# brushless_module_v2.net
KiCad netlist of a schematic drawn in EAGLE
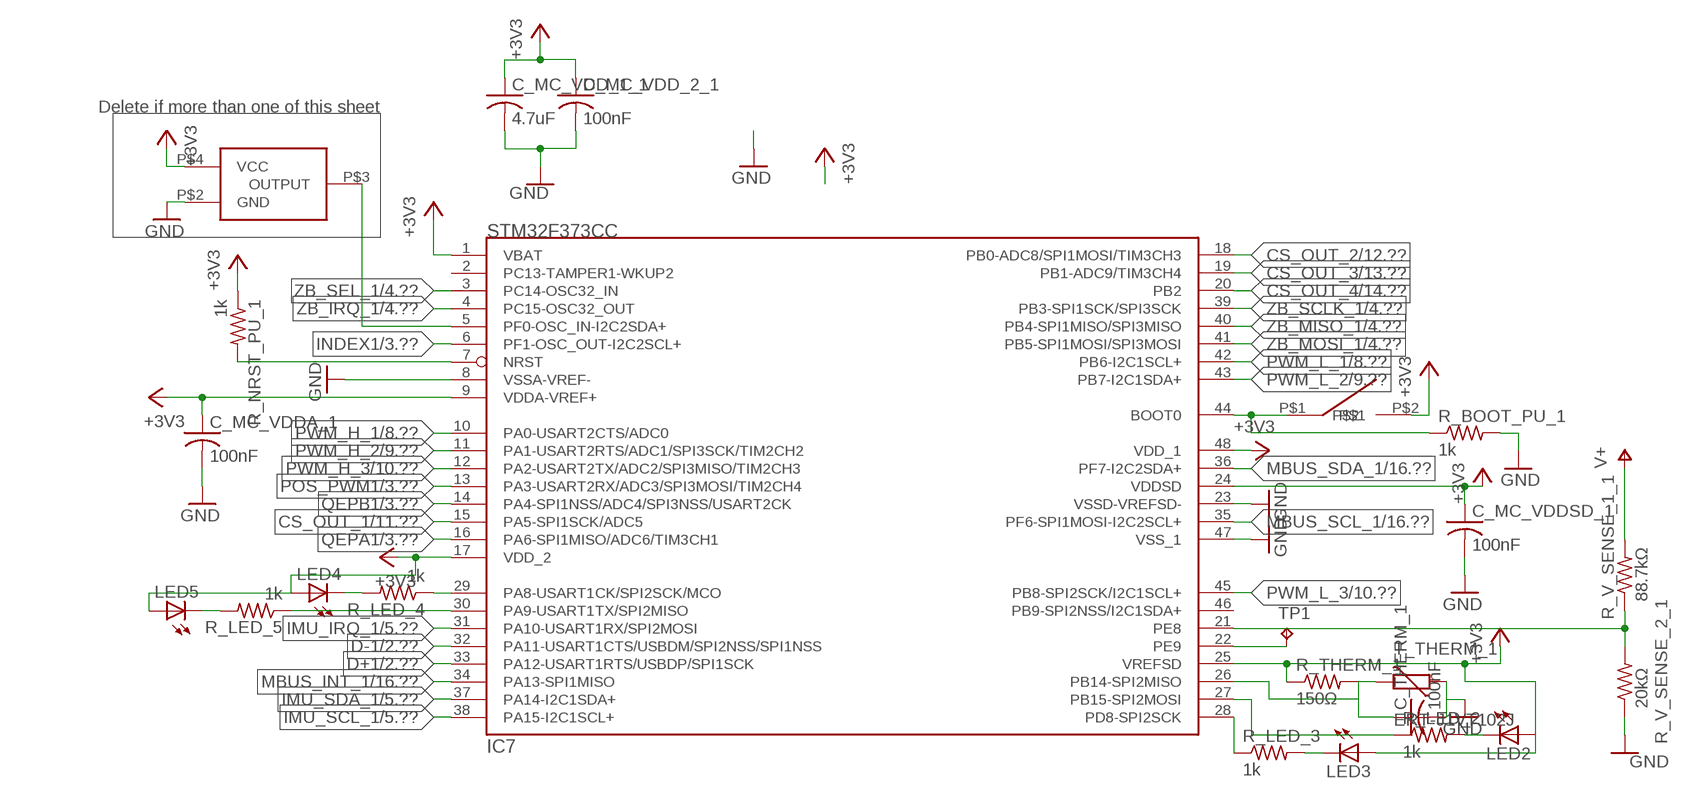
[diagram p0: schematic, sheet 1]
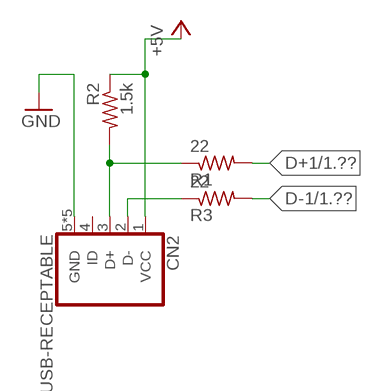
[diagram p1: schematic, sheet 2]
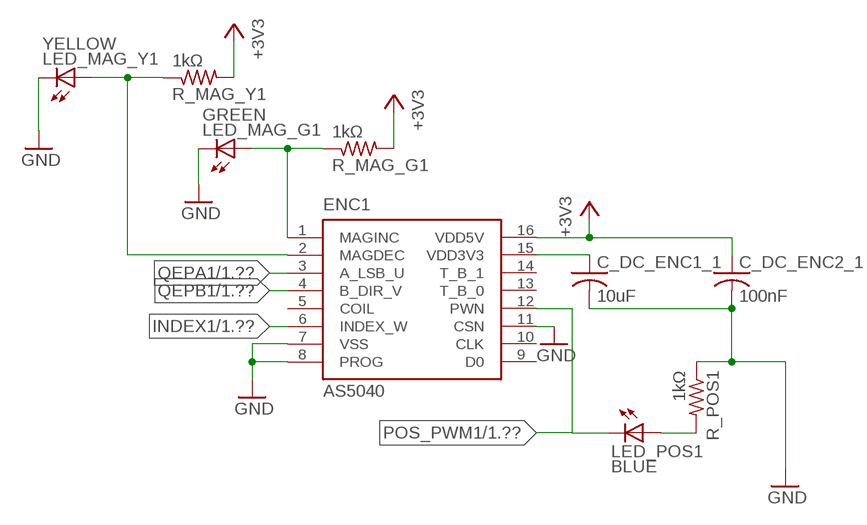
[diagram p2: schematic, sheet 3]
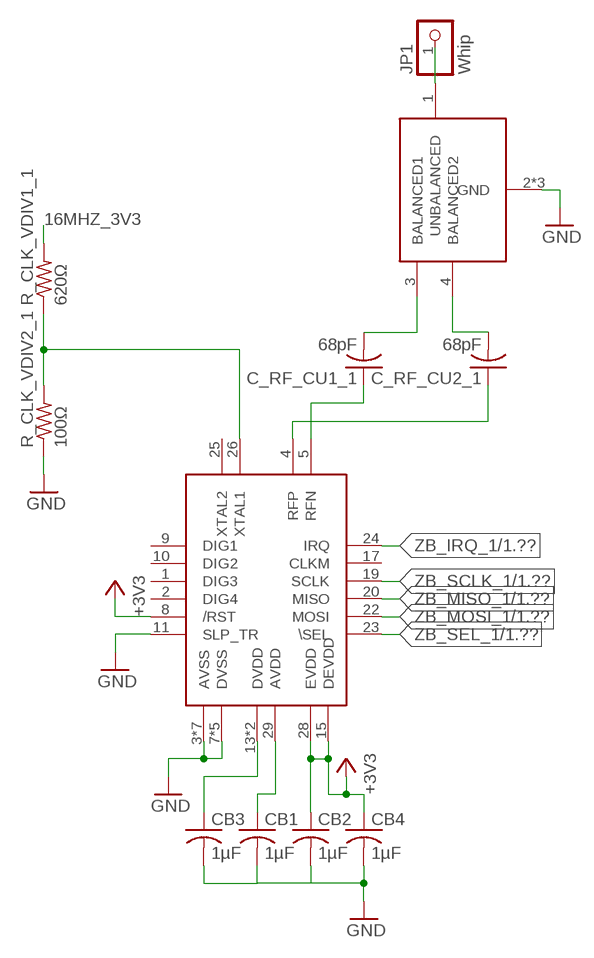
[diagram p3: schematic, sheet 4]
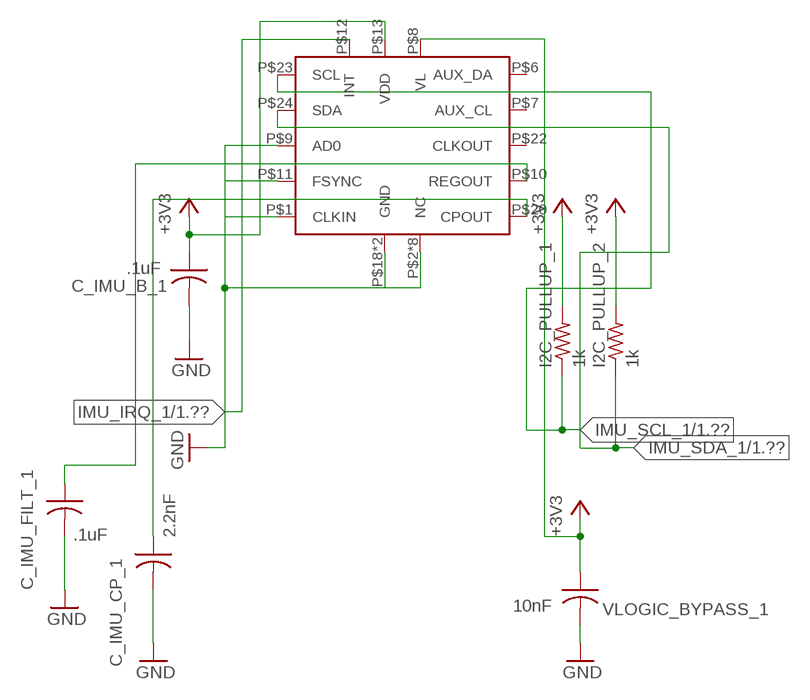
[diagram p4: schematic, sheet 5]
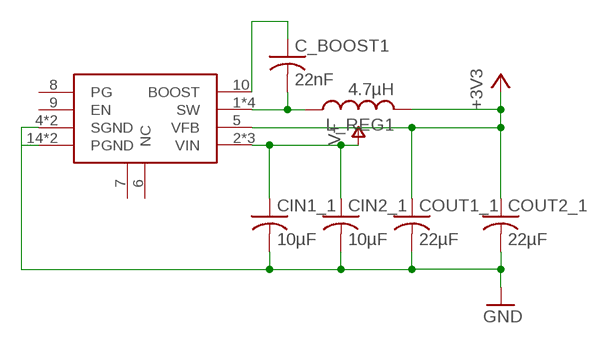
[diagram p5: schematic, sheet 6]
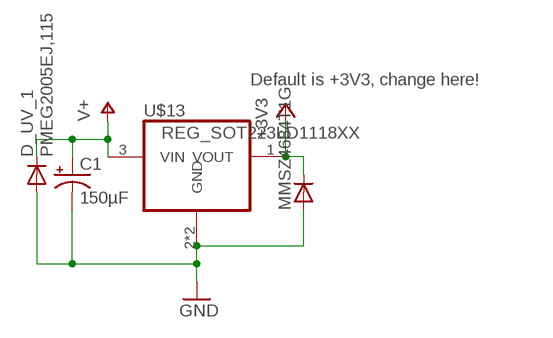
[diagram p6: schematic, sheet 7]
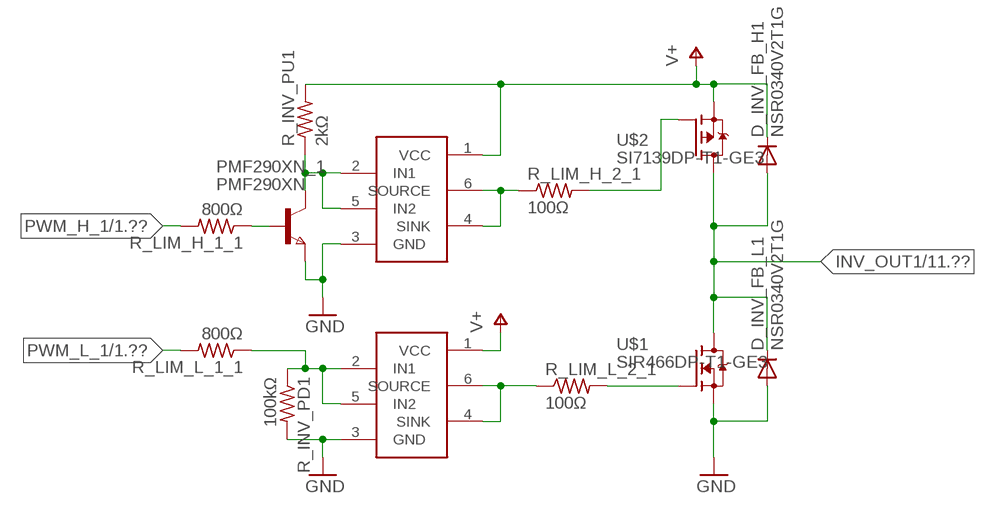
[diagram p7: schematic, sheet 8]
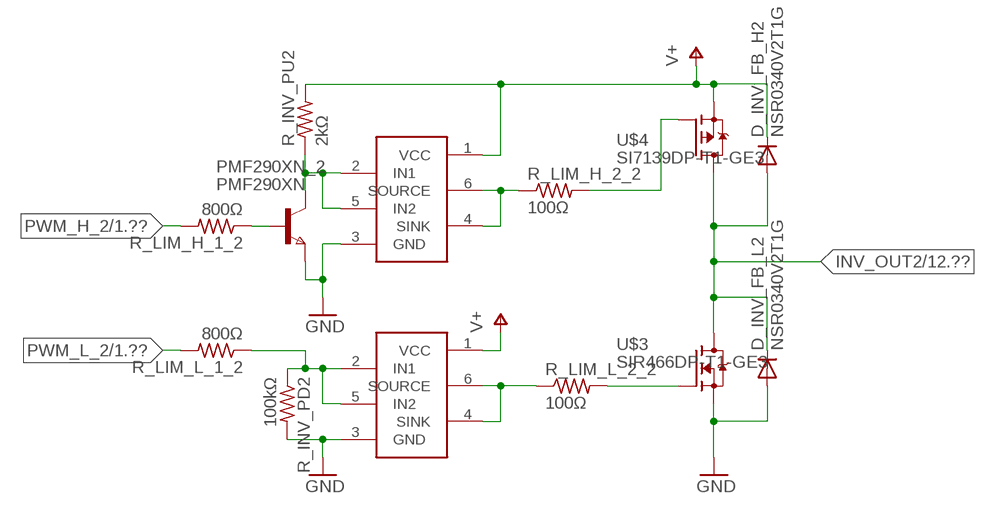
[diagram p8: schematic, sheet 9]
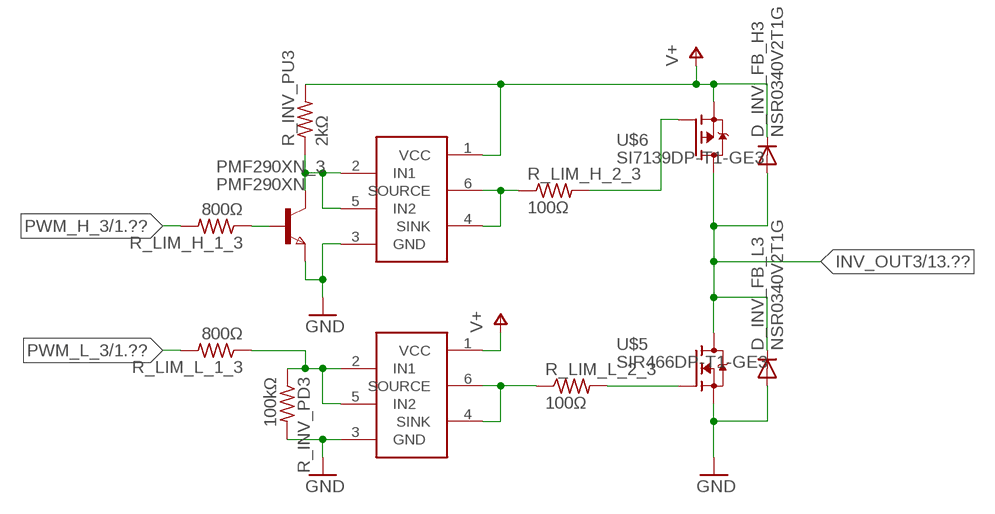
[diagram p9: schematic, sheet 10]
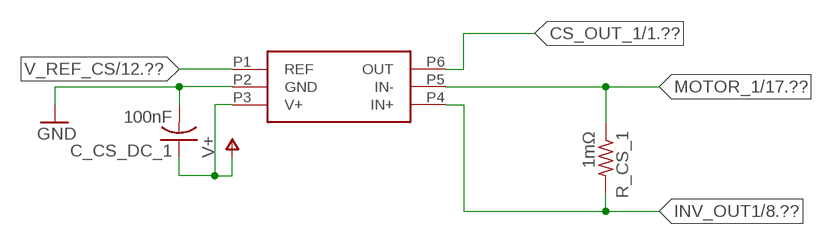
[diagram p10: schematic, sheet 11]
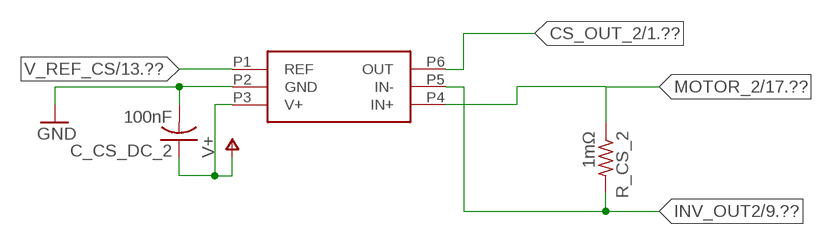
[diagram p11: schematic, sheet 12]
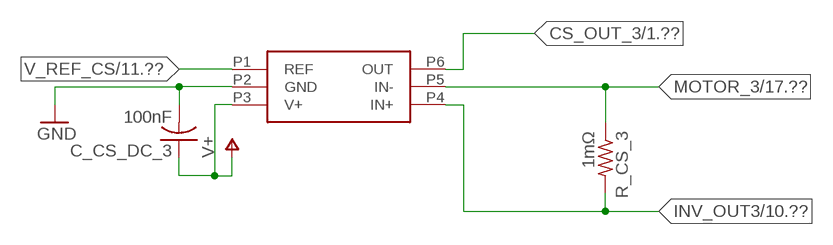
[diagram p12: schematic, sheet 13]
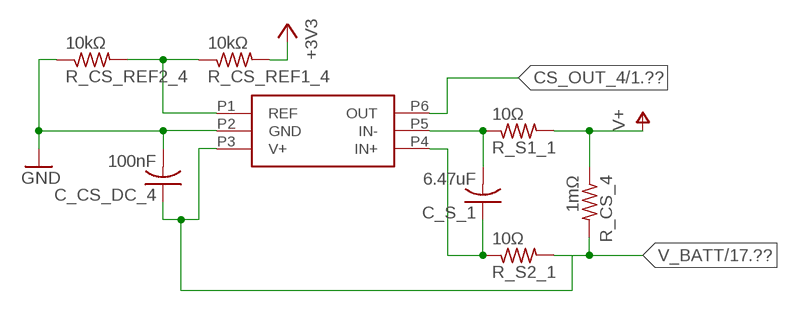
[diagram p13: schematic, sheet 14]
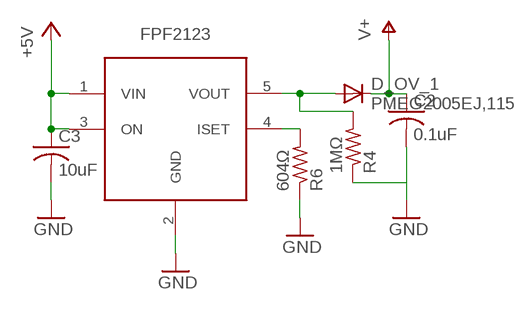
[diagram p14: schematic, sheet 15]
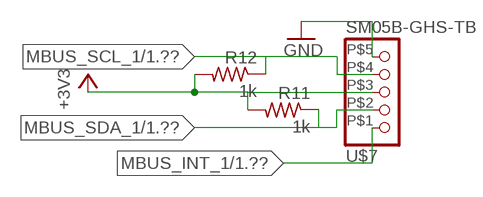
[diagram p15: schematic, sheet 16]
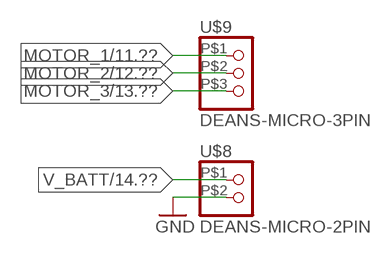
[diagram p16: schematic, sheet 17]

(export (version "E")
  (design (tool "Eeschema 10.0.6"))
  (components
    (comp (ref "C_DC_ENC1_1")
      (value "10uF")
      (footprint "eagle-import:C0603")
      (libsource (lib "eagle-import") (part "C-USC0603"))
    )
    (comp (ref "C_DC_ENC2_1")
      (value "100nF")
      (footprint "eagle-import:C0603")
      (libsource (lib "eagle-import") (part "C-USC0603"))
    )
    (comp (ref "ENC1")
      (value "AS5040")
      (footprint "eagle-import:SSOP16")
      (fields (field (name "MPN") "AS5040ASSU"))
      (libsource (lib "eagle-import") (part "AS5040"))
    )
    (comp (ref "LED_MAG_G1")
      (value "GREEN")
      (footprint "eagle-import:CHIP-LED0603")
      (libsource (lib "eagle-import") (part "LEDCHIP-LED0603"))
    )
    (comp (ref "LED_MAG_Y1")
      (value "YELLOW")
      (footprint "eagle-import:CHIP-LED0603")
      (libsource (lib "eagle-import") (part "LEDCHIP-LED0603"))
    )
    (comp (ref "LED_POS1")
      (value "BLUE")
      (footprint "eagle-import:CHIP-LED0603")
      (libsource (lib "eagle-import") (part "LEDCHIP-LED0603"))
    )
    (comp (ref "R_MAG_G1")
      (value "1kΩ")
      (footprint "eagle-import:R0603")
      (libsource (lib "eagle-import") (part "R-US_R0603"))
    )
    (comp (ref "R_MAG_Y1")
      (value "1kΩ")
      (footprint "eagle-import:R0603")
      (libsource (lib "eagle-import") (part "R-US_R0603"))
    )
    (comp (ref "R_POS1")
      (value "1kΩ")
      (footprint "eagle-import:R0603")
      (libsource (lib "eagle-import") (part "R-US_R0603"))
    )
    (comp (ref "U$8")
      (value "DEANS-MICRO-2PIN")
      (footprint "eagle-import:DEANS-MICRO-2PIN")
      (libsource (lib "eagle-import") (part "DEANS-MICRO-2PIN"))
    )
    (comp (ref "U$9")
      (value "DEANS-MICRO-3PIN")
      (footprint "eagle-import:DEANS-MICRO-3PIN")
      (libsource (lib "eagle-import") (part "DEANS-MICRO-3PIN"))
    )
    (comp (ref "C2")
      (value "0.1uF")
      (footprint "eagle-import:C0603")
      (libsource (lib "eagle-import") (part "C-USC0603"))
    )
    (comp (ref "C3")
      (value "10uF")
      (footprint "eagle-import:C0603")
      (libsource (lib "eagle-import") (part "C-USC0603"))
    )
    (comp (ref "D_OV_1")
      (value "PMEG2005EJ,115")
      (footprint "eagle-import:SOD323-W")
      (libsource (lib "eagle-import") (part "DIODE-SOD323-W"))
    )
    (comp (ref "FPF2123")
      (value "FPF2123")
      (footprint "eagle-import:SOT23-5L")
      (libsource (lib "eagle-import") (part "FPF2123"))
    )
    (comp (ref "R4")
      (value "1MΩ")
      (footprint "eagle-import:R0603")
      (libsource (lib "eagle-import") (part "R-US_R0603"))
    )
    (comp (ref "R6")
      (value "604Ω")
      (footprint "eagle-import:R0603")
      (libsource (lib "eagle-import") (part "R-US_R0603"))
    )
    (comp (ref "C_MC_VDDA_1")
      (value "100nF")
      (footprint "eagle-import:C0603")
      (libsource (lib "eagle-import") (part "C-USC0603"))
    )
    (comp (ref "C_MC_VDDSD_1")
      (value "100nF")
      (footprint "eagle-import:C0603")
      (libsource (lib "eagle-import") (part "C-USC0603"))
    )
    (comp (ref "C_MC_VDD_1_1")
      (value "4.7uF")
      (footprint "eagle-import:C0603")
      (libsource (lib "eagle-import") (part "C-USC0603"))
    )
    (comp (ref "C_MC_VDD_2_1")
      (value "100nF")
      (footprint "eagle-import:C0603")
      (libsource (lib "eagle-import") (part "C-USC0603"))
    )
    (comp (ref "C_THERM_1")
      (value "100nF")
      (footprint "eagle-import:C0603")
      (libsource (lib "eagle-import") (part "C-USC0603"))
    )
    (comp (ref "IC7")
      (value "STM32F373CC")
      (footprint "eagle-import:LQFP48")
      (libsource (lib "eagle-import") (part "STM32F373CC"))
    )
    (comp (ref "LED2")
      (value "LEDCHIPLED_0603")
      (footprint "eagle-import:CHIPLED_0603")
      (libsource (lib "eagle-import") (part "LEDCHIPLED_0603"))
    )
    (comp (ref "LED3")
      (value "LEDCHIPLED_0603")
      (footprint "eagle-import:CHIPLED_0603")
      (libsource (lib "eagle-import") (part "LEDCHIPLED_0603"))
    )
    (comp (ref "LED4")
      (value "LEDCHIPLED_0603")
      (footprint "eagle-import:CHIPLED_0603")
      (libsource (lib "eagle-import") (part "LEDCHIPLED_0603"))
    )
    (comp (ref "LED5")
      (value "LEDCHIPLED_0603")
      (footprint "eagle-import:CHIPLED_0603")
      (libsource (lib "eagle-import") (part "LEDCHIPLED_0603"))
    )
    (comp (ref "OSC1")
      (value "FOX924B")
      (footprint "eagle-import:4-SMD_5X3.2")
      (libsource (lib "eagle-import") (part "FOX924B"))
    )
    (comp (ref "R_BOOT_PU_1")
      (value "1k")
      (footprint "eagle-import:R0603")
      (libsource (lib "eagle-import") (part "R-US_R0603"))
    )
    (comp (ref "R_LED_2")
      (value "1k")
      (footprint "eagle-import:R0603")
      (libsource (lib "eagle-import") (part "R-US_R0603"))
    )
    (comp (ref "R_LED_3")
      (value "1k")
      (footprint "eagle-import:R0603")
      (libsource (lib "eagle-import") (part "R-US_R0603"))
    )
    (comp (ref "R_LED_4")
      (value "1k")
      (footprint "eagle-import:R0603")
      (libsource (lib "eagle-import") (part "R-US_R0603"))
    )
    (comp (ref "R_LED_5")
      (value "1k")
      (footprint "eagle-import:R0603")
      (libsource (lib "eagle-import") (part "R-US_R0603"))
    )
    (comp (ref "R_NRST_PU_1")
      (value "1k")
      (footprint "eagle-import:R0603")
      (libsource (lib "eagle-import") (part "R-US_R0603"))
    )
    (comp (ref "R_THERM_1")
      (value "150Ω")
      (footprint "eagle-import:R0603")
      (libsource (lib "eagle-import") (part "R-US_R0603"))
    )
    (comp (ref "R_V_SENSE_1_1")
      (value "88.7kΩ")
      (footprint "eagle-import:R0603")
      (libsource (lib "eagle-import") (part "R-US_R0603"))
    )
    (comp (ref "R_V_SENSE_2_1")
      (value "20kΩ")
      (footprint "eagle-import:R0603")
      (libsource (lib "eagle-import") (part "R-US_R0603"))
    )
    (comp (ref "SW1")
      (value "B3U")
      (footprint "eagle-import:B3U")
      (libsource (lib "eagle-import") (part "B3U"))
    )
    (comp (ref "TP1")
      (value "TPTP10R")
      (footprint "eagle-import:TP10R")
      (libsource (lib "eagle-import") (part "TPTP10R"))
    )
    (comp (ref "T_THERM_1")
      (value "ERT-J1VT102J")
      (footprint "eagle-import:CT_CN0603")
      (libsource (lib "eagle-import") (part "VARISTORCN0603"))
    )
    (comp (ref "D_INV_FB_H1")
      (value "NSR0340V2T1G")
      (footprint "eagle-import:SOD523")
      (libsource (lib "eagle-import") (part "DIODE-SOD523"))
    )
    (comp (ref "D_INV_FB_L1")
      (value "NSR0340V2T1G")
      (footprint "eagle-import:SOD523")
      (libsource (lib "eagle-import") (part "DIODE-SOD523"))
    )
    (comp (ref "PMF290XN_1")
      (value "PMF290XN")
      (footprint "eagle-import:SOT323")
      (fields (field (name "MPN") "DSS4160U-7"))
      (libsource (lib "eagle-import") (part "NPNSOT323"))
    )
    (comp (ref "R_INV_PD1")
      (value "100kΩ")
      (footprint "eagle-import:R0603")
      (fields (field (name "PART#") "RNCP0603FTD825RCT-ND"))
      (libsource (lib "eagle-import") (part "R-US_R0603"))
    )
    (comp (ref "R_INV_PU1")
      (value "2kΩ")
      (footprint "eagle-import:R0603")
      (libsource (lib "eagle-import") (part "R-US_R0603"))
    )
    (comp (ref "R_LIM_H_1_1")
      (value "800Ω")
      (footprint "eagle-import:R0603")
      (libsource (lib "eagle-import") (part "R-US_R0603"))
    )
    (comp (ref "R_LIM_H_2_1")
      (value "100Ω")
      (footprint "eagle-import:R0603")
      (libsource (lib "eagle-import") (part "R-US_R0603"))
    )
    (comp (ref "R_LIM_L_1_1")
      (value "800Ω")
      (footprint "eagle-import:R0603")
      (libsource (lib "eagle-import") (part "R-US_R0603"))
    )
    (comp (ref "R_LIM_L_2_1")
      (value "100Ω")
      (footprint "eagle-import:R0603")
      (libsource (lib "eagle-import") (part "R-US_R0603"))
    )
    (comp (ref "U$1")
      (value "SIR466DP-T1-GE3")
      (footprint "eagle-import:S0-8-POWERPAK")
      (libsource (lib "eagle-import") (part "SIR466DP-T1-GE3"))
    )
    (comp (ref "U$2")
      (value "SI7139DP-T1-GE3")
      (footprint "eagle-import:S0-8-POWERPAK")
      (libsource (lib "eagle-import") (part "SI7139DP-T1-GE3"))
    )
    (comp (ref "ZXGD3004E6_H_1")
      (value "ZXGD3004E6")
      (footprint "eagle-import:SOT23-6")
      (libsource (lib "eagle-import") (part "ZXGD3004E6"))
    )
    (comp (ref "ZXGD3004E6_L_1")
      (value "ZXGD3004E6")
      (footprint "eagle-import:SOT23-6")
      (libsource (lib "eagle-import") (part "ZXGD3004E6"))
    )
    (comp (ref "CN2")
      (value "USB-RECEPTABLE")
      (footprint "eagle-import:FCI-10103594-0001LF")
      (libsource (lib "eagle-import") (part "USB-RECEPTABLE"))
    )
    (comp (ref "R1")
      (value "22")
      (footprint "eagle-import:R0603")
      (libsource (lib "eagle-import") (part "R-US_R0603"))
    )
    (comp (ref "R2")
      (value "1.5k")
      (footprint "eagle-import:R0603")
      (libsource (lib "eagle-import") (part "R-US_R0603"))
    )
    (comp (ref "R3")
      (value "22")
      (footprint "eagle-import:R0603")
      (libsource (lib "eagle-import") (part "R-US_R0603"))
    )
    (comp (ref "C1")
      (value "150µF")
      (footprint "eagle-import:D_7343-31R")
      (libsource (lib "eagle-import") (part "CPOL-USD/7343-31R"))
    )
    (comp (ref "D_UV_1")
      (value "PMEG2005EJ,115")
      (footprint "eagle-import:SOD323-W")
      (libsource (lib "eagle-import") (part "DIODE-SOD323-W"))
    )
    (comp (ref "MMSZ4684T1G")
      (value "D-SOD123")
      (footprint "eagle-import:SOD123")
      (libsource (lib "eagle-import") (part "D-SOD123"))
    )
    (comp (ref "U$13")
      (value "REG_SOT223LD1118XX")
      (footprint "eagle-import:SOT-223")
      (libsource (lib "eagle-import") (part "REG_SOT223LD1118XX"))
    )
    (comp (ref "R11")
      (value "1k")
      (footprint "eagle-import:R0603")
      (libsource (lib "eagle-import") (part "R-US_R0603"))
    )
    (comp (ref "R12")
      (value "1k")
      (footprint "eagle-import:R0603")
      (libsource (lib "eagle-import") (part "R-US_R0603"))
    )
    (comp (ref "U$7")
      (value "SM05B-GHS-TB")
      (footprint "eagle-import:SM05B-GHS-TB")
      (libsource (lib "eagle-import") (part "SM05B-GHS-TB"))
    )
    (comp (ref "D_INV_FB_H2")
      (value "NSR0340V2T1G")
      (footprint "eagle-import:SOD523")
      (libsource (lib "eagle-import") (part "DIODE-SOD523"))
    )
    (comp (ref "D_INV_FB_L2")
      (value "NSR0340V2T1G")
      (footprint "eagle-import:SOD523")
      (libsource (lib "eagle-import") (part "DIODE-SOD523"))
    )
    (comp (ref "PMF290XN_2")
      (value "PMF290XN")
      (footprint "eagle-import:SOT323")
      (fields (field (name "MPN") "DSS4160U-7"))
      (libsource (lib "eagle-import") (part "NPNSOT323"))
    )
    (comp (ref "R_INV_PD2")
      (value "100kΩ")
      (footprint "eagle-import:R0603")
      (fields (field (name "PART#") "RNCP0603FTD825RCT-ND"))
      (libsource (lib "eagle-import") (part "R-US_R0603"))
    )
    (comp (ref "R_INV_PU2")
      (value "2kΩ")
      (footprint "eagle-import:R0603")
      (libsource (lib "eagle-import") (part "R-US_R0603"))
    )
    (comp (ref "R_LIM_H_1_2")
      (value "800Ω")
      (footprint "eagle-import:R0603")
      (libsource (lib "eagle-import") (part "R-US_R0603"))
    )
    (comp (ref "R_LIM_H_2_2")
      (value "100Ω")
      (footprint "eagle-import:R0603")
      (libsource (lib "eagle-import") (part "R-US_R0603"))
    )
    (comp (ref "R_LIM_L_1_2")
      (value "800Ω")
      (footprint "eagle-import:R0603")
      (libsource (lib "eagle-import") (part "R-US_R0603"))
    )
    (comp (ref "R_LIM_L_2_2")
      (value "100Ω")
      (footprint "eagle-import:R0603")
      (libsource (lib "eagle-import") (part "R-US_R0603"))
    )
    (comp (ref "U$3")
      (value "SIR466DP-T1-GE3")
      (footprint "eagle-import:S0-8-POWERPAK")
      (libsource (lib "eagle-import") (part "SIR466DP-T1-GE3"))
    )
    (comp (ref "U$4")
      (value "SI7139DP-T1-GE3")
      (footprint "eagle-import:S0-8-POWERPAK")
      (libsource (lib "eagle-import") (part "SI7139DP-T1-GE3"))
    )
    (comp (ref "ZXGD3004E6_H_2")
      (value "ZXGD3004E6")
      (footprint "eagle-import:SOT23-6")
      (libsource (lib "eagle-import") (part "ZXGD3004E6"))
    )
    (comp (ref "ZXGD3004E6_L_2")
      (value "ZXGD3004E6")
      (footprint "eagle-import:SOT23-6")
      (libsource (lib "eagle-import") (part "ZXGD3004E6"))
    )
    (comp (ref "C_IMU_B_1")
      (value ".1uF")
      (footprint "eagle-import:C0603")
      (libsource (lib "eagle-import") (part "C-USC0603"))
    )
    (comp (ref "C_IMU_CP_1")
      (value "2.2nF")
      (footprint "eagle-import:C0603")
      (libsource (lib "eagle-import") (part "C-USC0603"))
    )
    (comp (ref "C_IMU_FILT_1")
      (value ".1uF")
      (footprint "eagle-import:C0603")
      (libsource (lib "eagle-import") (part "C-USC0603"))
    )
    (comp (ref "I2C_PULLUP_1")
      (value "1k")
      (footprint "eagle-import:R0603")
      (libsource (lib "eagle-import") (part "R-US_R0603"))
    )
    (comp (ref "I2C_PULLUP_2")
      (value "1k")
      (footprint "eagle-import:R0603")
      (libsource (lib "eagle-import") (part "R-US_R0603"))
    )
    (comp (ref "U$10")
      (value "MPU-6050")
      (footprint "eagle-import:QFN24")
      (libsource (lib "eagle-import") (part "MPU-6050"))
    )
    (comp (ref "VLOGIC_BYPASS_1")
      (value "10nF")
      (footprint "eagle-import:C0603")
      (libsource (lib "eagle-import") (part "C-USC0603"))
    )
    (comp (ref "CIN1_1")
      (value "10µF")
      (footprint "eagle-import:C0805")
      (libsource (lib "eagle-import") (part "C-USC0805"))
    )
    (comp (ref "CIN2_1")
      (value "10µF")
      (footprint "eagle-import:C0805")
      (libsource (lib "eagle-import") (part "C-USC0805"))
    )
    (comp (ref "COUT1_1")
      (value "22µF")
      (footprint "eagle-import:C0603")
      (libsource (lib "eagle-import") (part "C-USC0603"))
    )
    (comp (ref "COUT2_1")
      (value "22µF")
      (footprint "eagle-import:C0603")
      (libsource (lib "eagle-import") (part "C-USC0603"))
    )
    (comp (ref "C_BOOST1")
      (value "22nF")
      (footprint "eagle-import:C0603")
      (libsource (lib "eagle-import") (part "C-USC0603"))
    )
    (comp (ref "L_REG1")
      (value "4.7µH")
      (footprint "eagle-import:VLC5045")
      (libsource (lib "eagle-import") (part "VLC5045"))
    )
    (comp (ref "SW_REG1")
      (value "MCP16323")
      (footprint "eagle-import:QFN16")
      (libsource (lib "eagle-import") (part "MCP16323"))
    )
    (comp (ref "CS_1")
      (value "INA21X")
      (footprint "eagle-import:SC70")
      (libsource (lib "eagle-import") (part "INA21X"))
    )
    (comp (ref "C_CS_DC_1")
      (value "100nF")
      (footprint "eagle-import:C0603")
      (libsource (lib "eagle-import") (part "C-USC0603"))
    )
    (comp (ref "R_CS_1")
      (value "1mΩ")
      (footprint "eagle-import:R1206")
      (libsource (lib "eagle-import") (part "R-US_R1206"))
    )
    (comp (ref "BALUN1")
      (value "0896FB15A0100")
      (footprint "eagle-import:0896FB15A0100")
      (libsource (lib "eagle-import") (part "0896FB15A0100"))
    )
    (comp (ref "CB1")
      (value "1µF")
      (footprint "eagle-import:C0603")
      (libsource (lib "eagle-import") (part "C-USC0603"))
    )
    (comp (ref "CB2")
      (value "1µF")
      (footprint "eagle-import:C0603")
      (libsource (lib "eagle-import") (part "C-USC0603"))
    )
    (comp (ref "CB3")
      (value "1µF")
      (footprint "eagle-import:C0603")
      (libsource (lib "eagle-import") (part "C-USC0603"))
    )
    (comp (ref "CB4")
      (value "1µF")
      (footprint "eagle-import:C0603")
      (libsource (lib "eagle-import") (part "C-USC0603"))
    )
    (comp (ref "C_RF_CU1_1")
      (value "68pF")
      (footprint "eagle-import:C0603")
      (libsource (lib "eagle-import") (part "C-USC0603"))
    )
    (comp (ref "C_RF_CU2_1")
      (value "68pF")
      (footprint "eagle-import:C0603")
      (libsource (lib "eagle-import") (part "C-USC0603"))
    )
    (comp (ref "JP1")
      (value "Whip")
      (footprint "eagle-import:1X01M")
      (libsource (lib "eagle-import") (part "PINHD-1X01_2.00"))
    )
    (comp (ref "RADIO1")
      (value "AT86RF")
      (footprint "eagle-import:QFNN32")
      (libsource (lib "eagle-import") (part "AT86RF"))
    )
    (comp (ref "R_CLK_VDIV1_1")
      (value "620Ω")
      (footprint "eagle-import:R0603")
      (libsource (lib "eagle-import") (part "R-US_R0603"))
    )
    (comp (ref "R_CLK_VDIV2_1")
      (value "100Ω")
      (footprint "eagle-import:R0603")
      (libsource (lib "eagle-import") (part "R-US_R0603"))
    )
    (comp (ref "D_INV_FB_H3")
      (value "NSR0340V2T1G")
      (footprint "eagle-import:SOD523")
      (libsource (lib "eagle-import") (part "DIODE-SOD523"))
    )
    (comp (ref "D_INV_FB_L3")
      (value "NSR0340V2T1G")
      (footprint "eagle-import:SOD523")
      (libsource (lib "eagle-import") (part "DIODE-SOD523"))
    )
    (comp (ref "PMF290XN_3")
      (value "PMF290XN")
      (footprint "eagle-import:SOT323")
      (fields (field (name "MPN") "DSS4160U-7"))
      (libsource (lib "eagle-import") (part "NPNSOT323"))
    )
    (comp (ref "R_INV_PD3")
      (value "100kΩ")
      (footprint "eagle-import:R0603")
      (fields (field (name "PART#") "RNCP0603FTD825RCT-ND"))
      (libsource (lib "eagle-import") (part "R-US_R0603"))
    )
    (comp (ref "R_INV_PU3")
      (value "2kΩ")
      (footprint "eagle-import:R0603")
      (libsource (lib "eagle-import") (part "R-US_R0603"))
    )
    (comp (ref "R_LIM_H_1_3")
      (value "800Ω")
      (footprint "eagle-import:R0603")
      (libsource (lib "eagle-import") (part "R-US_R0603"))
    )
    (comp (ref "R_LIM_H_2_3")
      (value "100Ω")
      (footprint "eagle-import:R0603")
      (libsource (lib "eagle-import") (part "R-US_R0603"))
    )
    (comp (ref "R_LIM_L_1_3")
      (value "800Ω")
      (footprint "eagle-import:R0603")
      (libsource (lib "eagle-import") (part "R-US_R0603"))
    )
    (comp (ref "R_LIM_L_2_3")
      (value "100Ω")
      (footprint "eagle-import:R0603")
      (libsource (lib "eagle-import") (part "R-US_R0603"))
    )
    (comp (ref "U$5")
      (value "SIR466DP-T1-GE3")
      (footprint "eagle-import:S0-8-POWERPAK")
      (libsource (lib "eagle-import") (part "SIR466DP-T1-GE3"))
    )
    (comp (ref "U$6")
      (value "SI7139DP-T1-GE3")
      (footprint "eagle-import:S0-8-POWERPAK")
      (libsource (lib "eagle-import") (part "SI7139DP-T1-GE3"))
    )
    (comp (ref "ZXGD3004E6_H_3")
      (value "ZXGD3004E6")
      (footprint "eagle-import:SOT23-6")
      (libsource (lib "eagle-import") (part "ZXGD3004E6"))
    )
    (comp (ref "ZXGD3004E6_L_3")
      (value "ZXGD3004E6")
      (footprint "eagle-import:SOT23-6")
      (libsource (lib "eagle-import") (part "ZXGD3004E6"))
    )
    (comp (ref "CS_4")
      (value "INA21X")
      (footprint "eagle-import:SC70")
      (libsource (lib "eagle-import") (part "INA21X"))
    )
    (comp (ref "C_CS_DC_4")
      (value "100nF")
      (footprint "eagle-import:C0603")
      (libsource (lib "eagle-import") (part "C-USC0603"))
    )
    (comp (ref "C_S_1")
      (value "6.47uF")
      (footprint "eagle-import:C0603")
      (libsource (lib "eagle-import") (part "C-USC0603"))
    )
    (comp (ref "R_CS_4")
      (value "1mΩ")
      (footprint "eagle-import:R1206")
      (libsource (lib "eagle-import") (part "R-US_R1206"))
    )
    (comp (ref "R_CS_REF1_4")
      (value "10kΩ")
      (footprint "eagle-import:R0603")
      (libsource (lib "eagle-import") (part "R-US_R0603"))
    )
    (comp (ref "R_CS_REF2_4")
      (value "10kΩ")
      (footprint "eagle-import:R0603")
      (libsource (lib "eagle-import") (part "R-US_R0603"))
    )
    (comp (ref "R_S1_1")
      (value "10Ω")
      (footprint "eagle-import:R0603")
      (libsource (lib "eagle-import") (part "R-US_R0603"))
    )
    (comp (ref "R_S2_1")
      (value "10Ω")
      (footprint "eagle-import:R0603")
      (libsource (lib "eagle-import") (part "R-US_R0603"))
    )
    (comp (ref "CS_2")
      (value "INA21X")
      (footprint "eagle-import:SC70")
      (libsource (lib "eagle-import") (part "INA21X"))
    )
    (comp (ref "C_CS_DC_2")
      (value "100nF")
      (footprint "eagle-import:C0603")
      (libsource (lib "eagle-import") (part "C-USC0603"))
    )
    (comp (ref "R_CS_2")
      (value "1mΩ")
      (footprint "eagle-import:R1206")
      (libsource (lib "eagle-import") (part "R-US_R1206"))
    )
    (comp (ref "CS_3")
      (value "INA21X")
      (footprint "eagle-import:SC70")
      (libsource (lib "eagle-import") (part "INA21X"))
    )
    (comp (ref "C_CS_DC_3")
      (value "100nF")
      (footprint "eagle-import:C0603")
      (libsource (lib "eagle-import") (part "C-USC0603"))
    )
    (comp (ref "R_CS_3")
      (value "1mΩ")
      (footprint "eagle-import:R1206")
      (libsource (lib "eagle-import") (part "R-US_R1206"))
    )
  )
  (nets
    (net (code "1") (name "+3V3") (class "Default")
      (node (ref "CB2") (pin "1") (pinfunction "1_1") (pintype "passive"))
      (node (ref "CB4") (pin "1") (pinfunction "1_1") (pintype "passive"))
      (node (ref "COUT1_1") (pin "1") (pinfunction "1_1") (pintype "passive"))
      (node (ref "COUT2_1") (pin "1") (pinfunction "1_1") (pintype "passive"))
      (node (ref "C_DC_ENC2_1") (pin "1") (pinfunction "1_1") (pintype "passive"))
      (node (ref "C_IMU_B_1") (pin "1") (pinfunction "1_1") (pintype "passive"))
      (node (ref "C_MC_VDDA_1") (pin "1") (pinfunction "1_1") (pintype "passive"))
      (node (ref "C_MC_VDDSD_1") (pin "1") (pinfunction "1_1") (pintype "passive"))
      (node (ref "C_MC_VDD_1_1") (pin "1") (pinfunction "1_1") (pintype "passive"))
      (node (ref "C_MC_VDD_2_1") (pin "1") (pinfunction "1_1") (pintype "passive"))
      (node (ref "ENC1") (pin "16") (pinfunction "VDD5V_16") (pintype "passive"))
      (node (ref "I2C_PULLUP_1") (pin "2") (pinfunction "2_2") (pintype "passive"))
      (node (ref "I2C_PULLUP_2") (pin "2") (pinfunction "2_2") (pintype "passive"))
      (node (ref "IC7") (pin "1") (pinfunction "VBAT_1") (pintype "power_in"))
      (node (ref "IC7") (pin "17") (pinfunction "VDD_2_17") (pintype "bidirectional"))
      (node (ref "IC7") (pin "24") (pinfunction "VDDSD_24") (pintype "power_in"))
      (node (ref "IC7") (pin "25") (pinfunction "VREFSD_25") (pintype "bidirectional"))
      (node (ref "IC7") (pin "48") (pinfunction "VDD_1_48") (pintype "power_in"))
      (node (ref "IC7") (pin "9") (pinfunction "VDDA-VREF+_9") (pintype "power_in"))
      (node (ref "LED2") (pin "A") (pinfunction "A_A") (pintype "passive"))
      (node (ref "LED3") (pin "A") (pinfunction "A_A") (pintype "passive"))
      (node (ref "LED4") (pin "A") (pinfunction "A_A") (pintype "passive"))
      (node (ref "LED5") (pin "A") (pinfunction "A_A") (pintype "passive"))
      (node (ref "L_REG1") (pin "2") (pinfunction "2_2") (pintype "passive"))
      (node (ref "MMSZ4684T1G") (pin "1") (pinfunction "C_1") (pintype "passive"))
      (node (ref "OSC1") (pin "P$4") (pinfunction "VCC_P$4") (pintype "bidirectional"))
      (node (ref "R11") (pin "2") (pinfunction "2_2") (pintype "passive"))
      (node (ref "R12") (pin "2") (pinfunction "2_2") (pintype "passive"))
      (node (ref "RADIO1") (pin "15") (pinfunction "DEVDD_15") (pintype "power_in"))
      (node (ref "RADIO1") (pin "28") (pinfunction "EVDD_28") (pintype "power_in"))
      (node (ref "RADIO1") (pin "8") (pinfunction "/RST_8") (pintype "input"))
      (node (ref "R_CS_REF1_4") (pin "2") (pinfunction "2_2") (pintype "passive"))
      (node (ref "R_MAG_G1") (pin "2") (pinfunction "2_2") (pintype "passive"))
      (node (ref "R_MAG_Y1") (pin "2") (pinfunction "2_2") (pintype "passive"))
      (node (ref "R_NRST_PU_1") (pin "1") (pinfunction "1_1") (pintype "passive"))
      (node (ref "R_THERM_1") (pin "1") (pinfunction "1_1") (pintype "passive"))
      (node (ref "SW1") (pin "P$2") (pinfunction "P$2_P$2") (pintype "bidirectional"))
      (node (ref "SW_REG1") (pin "5") (pinfunction "VFB_5") (pintype "bidirectional"))
      (node (ref "U$10") (pin "P$13") (pinfunction "VDD_P$13") (pintype "bidirectional"))
      (node (ref "U$10") (pin "P$8") (pinfunction "VL_P$8") (pintype "bidirectional"))
      (node (ref "U$13") (pin "1") (pinfunction "VOUT_1") (pintype "output"))
      (node (ref "U$7") (pin "P$3") (pinfunction "3_P$3") (pintype "passive"))
      (node (ref "VLOGIC_BYPASS_1") (pin "1") (pinfunction "1_1") (pintype "passive"))
    )
    (net (code "2") (name "+5V") (class "Default")
      (node (ref "C3") (pin "1") (pinfunction "1_1") (pintype "passive"))
      (node (ref "CN2") (pin "1") (pinfunction "VCC_1") (pintype "bidirectional"))
      (node (ref "FPF2123") (pin "1") (pinfunction "VIN_1") (pintype "bidirectional"))
      (node (ref "FPF2123") (pin "3") (pinfunction "ON_3") (pintype "bidirectional"))
      (node (ref "R2") (pin "1") (pinfunction "1_1") (pintype "passive"))
    )
    (net (code "3") (name "16MHZ_3V3") (class "Default")
      (node (ref "IC7") (pin "5") (pinfunction "PF0-OSC_IN-I2C2SDA+_5") (pintype "bidirectional"))
      (node (ref "OSC1") (pin "P$3") (pinfunction "OUTPUT_P$3") (pintype "bidirectional"))
      (node (ref "R_CLK_VDIV1_1") (pin "2") (pinfunction "2_2") (pintype "passive"))
    )
    (net (code "4") (name "CS_OUT_1") (class "Default")
      (node (ref "CS_1") (pin "P6") (pinfunction "OUT_P6") (pintype "output"))
      (node (ref "IC7") (pin "15") (pinfunction "PA5-SPI1SCK/ADC5_15") (pintype "bidirectional"))
    )
    (net (code "5") (name "CS_OUT_2") (class "Default")
      (node (ref "CS_2") (pin "P6") (pinfunction "OUT_P6") (pintype "output"))
      (node (ref "IC7") (pin "18") (pinfunction "PB0-ADC8/SPI1MOSI/TIM3CH3_18") (pintype "bidirectional"))
    )
    (net (code "6") (name "CS_OUT_3") (class "Default")
      (node (ref "CS_3") (pin "P6") (pinfunction "OUT_P6") (pintype "output"))
      (node (ref "IC7") (pin "19") (pinfunction "PB1-ADC9/TIM3CH4_19") (pintype "bidirectional"))
    )
    (net (code "7") (name "CS_OUT_4") (class "Default")
      (node (ref "CS_4") (pin "P6") (pinfunction "OUT_P6") (pintype "output"))
      (node (ref "IC7") (pin "20") (pinfunction "PB2_20") (pintype "bidirectional"))
    )
    (net (code "8") (name "D+1") (class "Default")
      (node (ref "IC7") (pin "33") (pinfunction "PA12-USART1RTS/USBDP/SPI1SCK_33") (pintype "bidirectional"))
      (node (ref "R1") (pin "2") (pinfunction "2_2") (pintype "passive"))
    )
    (net (code "9") (name "D-1") (class "Default")
      (node (ref "IC7") (pin "32") (pinfunction "PA11-USART1CTS/USBDM/SPI2NSS/SPI1NSS_32") (pintype "bidirectional"))
      (node (ref "R3") (pin "2") (pinfunction "2_2") (pintype "passive"))
    )
    (net (code "10") (name "GND") (class "Default")
      (node (ref "BALUN1") (pin "2") (pinfunction "GND_2") (pintype "power_in"))
      (node (ref "BALUN1") (pin "5") (pinfunction "GND_5") (pintype "power_in"))
      (node (ref "BALUN1") (pin "6") (pinfunction "GND_6") (pintype "power_in"))
      (node (ref "C1") (pin "-") (pinfunction "-_-") (pintype "passive"))
      (node (ref "C2") (pin "2") (pinfunction "2_2") (pintype "passive"))
      (node (ref "C3") (pin "2") (pinfunction "2_2") (pintype "passive"))
      (node (ref "CB1") (pin "2") (pinfunction "2_2") (pintype "passive"))
      (node (ref "CB2") (pin "2") (pinfunction "2_2") (pintype "passive"))
      (node (ref "CB3") (pin "2") (pinfunction "2_2") (pintype "passive"))
      (node (ref "CB4") (pin "2") (pinfunction "2_2") (pintype "passive"))
      (node (ref "CIN1_1") (pin "2") (pinfunction "2_2") (pintype "passive"))
      (node (ref "CIN2_1") (pin "2") (pinfunction "2_2") (pintype "passive"))
      (node (ref "CN2") (pin "5") (pinfunction "GND_5") (pintype "bidirectional"))
      (node (ref "CN2") (pin "P$1") (pinfunction "GND_P$1") (pintype "bidirectional"))
      (node (ref "CN2") (pin "P$2") (pinfunction "GND_P$2") (pintype "bidirectional"))
      (node (ref "CN2") (pin "P$3") (pinfunction "GND_P$3") (pintype "bidirectional"))
      (node (ref "CN2") (pin "P$4") (pinfunction "GND_P$4") (pintype "bidirectional"))
      (node (ref "COUT1_1") (pin "2") (pinfunction "2_2") (pintype "passive"))
      (node (ref "COUT2_1") (pin "2") (pinfunction "2_2") (pintype "passive"))
      (node (ref "CS_1") (pin "P2") (pinfunction "GND_P2") (pintype "power_in"))
      (node (ref "CS_2") (pin "P2") (pinfunction "GND_P2") (pintype "power_in"))
      (node (ref "CS_3") (pin "P2") (pinfunction "GND_P2") (pintype "power_in"))
      (node (ref "CS_4") (pin "P2") (pinfunction "GND_P2") (pintype "power_in"))
      (node (ref "C_CS_DC_1") (pin "2") (pinfunction "2_2") (pintype "passive"))
      (node (ref "C_CS_DC_2") (pin "2") (pinfunction "2_2") (pintype "passive"))
      (node (ref "C_CS_DC_3") (pin "2") (pinfunction "2_2") (pintype "passive"))
      (node (ref "C_CS_DC_4") (pin "2") (pinfunction "2_2") (pintype "passive"))
      (node (ref "C_DC_ENC1_1") (pin "2") (pinfunction "2_2") (pintype "passive"))
      (node (ref "C_DC_ENC2_1") (pin "2") (pinfunction "2_2") (pintype "passive"))
      (node (ref "C_IMU_B_1") (pin "2") (pinfunction "2_2") (pintype "passive"))
      (node (ref "C_IMU_CP_1") (pin "2") (pinfunction "2_2") (pintype "passive"))
      (node (ref "C_IMU_FILT_1") (pin "2") (pinfunction "2_2") (pintype "passive"))
      (node (ref "C_MC_VDDA_1") (pin "2") (pinfunction "2_2") (pintype "passive"))
      (node (ref "C_MC_VDDSD_1") (pin "2") (pinfunction "2_2") (pintype "passive"))
      (node (ref "C_MC_VDD_1_1") (pin "2") (pinfunction "2_2") (pintype "passive"))
      (node (ref "C_MC_VDD_2_1") (pin "2") (pinfunction "2_2") (pintype "passive"))
      (node (ref "C_THERM_1") (pin "2") (pinfunction "2_2") (pintype "passive"))
      (node (ref "D_INV_FB_L1") (pin "A") (pinfunction "A_A") (pintype "passive"))
      (node (ref "D_INV_FB_L2") (pin "A") (pinfunction "A_A") (pintype "passive"))
      (node (ref "D_INV_FB_L3") (pin "A") (pinfunction "A_A") (pintype "passive"))
      (node (ref "D_UV_1") (pin "A") (pinfunction "A_A") (pintype "passive"))
      (node (ref "ENC1") (pin "11") (pinfunction "CSN_11") (pintype "input"))
      (node (ref "ENC1") (pin "7") (pinfunction "VSS_7") (pintype "passive"))
      (node (ref "ENC1") (pin "8") (pinfunction "PROG_8") (pintype "input"))
      (node (ref "FPF2123") (pin "2") (pinfunction "GND_2") (pintype "bidirectional"))
      (node (ref "IC7") (pin "23") (pinfunction "VSSD-VREFSD-_23") (pintype "power_in"))
      (node (ref "IC7") (pin "47") (pinfunction "VSS_1_47") (pintype "power_in"))
      (node (ref "IC7") (pin "8") (pinfunction "VSSA-VREF-_8") (pintype "power_in"))
      (node (ref "LED_MAG_G1") (pin "C") (pinfunction "C_C") (pintype "passive"))
      (node (ref "LED_MAG_Y1") (pin "C") (pinfunction "C_C") (pintype "passive"))
      (node (ref "MMSZ4684T1G") (pin "2") (pinfunction "A_2") (pintype "passive"))
      (node (ref "OSC1") (pin "P$2") (pinfunction "GND_P$2") (pintype "bidirectional"))
      (node (ref "PMF290XN_1") (pin "3") (pinfunction "E_3") (pintype "passive"))
      (node (ref "PMF290XN_2") (pin "3") (pinfunction "E_3") (pintype "passive"))
      (node (ref "PMF290XN_3") (pin "3") (pinfunction "E_3") (pintype "passive"))
      (node (ref "R4") (pin "1") (pinfunction "1_1") (pintype "passive"))
      (node (ref "R6") (pin "1") (pinfunction "1_1") (pintype "passive"))
      (node (ref "RADIO1") (pin "11") (pinfunction "SLP_TR_11") (pintype "bidirectional"))
      (node (ref "RADIO1") (pin "12") (pinfunction "DVSS_12") (pintype "power_in"))
      (node (ref "RADIO1") (pin "16") (pinfunction "DVSS_16") (pintype "power_in"))
      (node (ref "RADIO1") (pin "18") (pinfunction "DVSS_18") (pintype "power_in"))
      (node (ref "RADIO1") (pin "21") (pinfunction "DVSS_21") (pintype "power_in"))
      (node (ref "RADIO1") (pin "27") (pinfunction "AVSS_27") (pintype "power_in"))
      (node (ref "RADIO1") (pin "3") (pinfunction "AVSS_3") (pintype "power_in"))
      (node (ref "RADIO1") (pin "30") (pinfunction "AVSS_30") (pintype "power_in"))
      (node (ref "RADIO1") (pin "31") (pinfunction "AVSS_31") (pintype "power_in"))
      (node (ref "RADIO1") (pin "32") (pinfunction "AVSS_32") (pintype "power_in"))
      (node (ref "RADIO1") (pin "6") (pinfunction "AVSS_6") (pintype "power_in"))
      (node (ref "RADIO1") (pin "7") (pinfunction "DVSS_7") (pintype "power_in"))
      (node (ref "RADIO1") (pin "EXP") (pinfunction "AVSS_EXP") (pintype "power_in"))
      (node (ref "R_BOOT_PU_1") (pin "2") (pinfunction "2_2") (pintype "passive"))
      (node (ref "R_CLK_VDIV2_1") (pin "1") (pinfunction "1_1") (pintype "passive"))
      (node (ref "R_CS_REF2_4") (pin "1") (pinfunction "1_1") (pintype "passive"))
      (node (ref "R_INV_PD1") (pin "2") (pinfunction "2_2") (pintype "passive"))
      (node (ref "R_INV_PD2") (pin "2") (pinfunction "2_2") (pintype "passive"))
      (node (ref "R_INV_PD3") (pin "2") (pinfunction "2_2") (pintype "passive"))
      (node (ref "R_POS1") (pin "1") (pinfunction "1_1") (pintype "passive"))
      (node (ref "R_V_SENSE_2_1") (pin "1") (pinfunction "1_1") (pintype "passive"))
      (node (ref "SW_REG1") (pin "14") (pinfunction "PGND_14") (pintype "bidirectional"))
      (node (ref "SW_REG1") (pin "15") (pinfunction "PGND_15") (pintype "bidirectional"))
      (node (ref "SW_REG1") (pin "4") (pinfunction "SGND_4") (pintype "bidirectional"))
      (node (ref "SW_REG1") (pin "TH") (pinfunction "SGND_TH") (pintype "bidirectional"))
      (node (ref "T_THERM_1") (pin "1") (pinfunction "1_1") (pintype "passive"))
      (node (ref "U$1") (pin "1") (pinfunction "S_1") (pintype "passive"))
      (node (ref "U$1") (pin "2") (pinfunction "S_2") (pintype "passive"))
      (node (ref "U$1") (pin "3") (pinfunction "S_3") (pintype "passive"))
      (node (ref "U$10") (pin "P$1") (pinfunction "CLKIN_P$1") (pintype "bidirectional"))
      (node (ref "U$10") (pin "P$11") (pinfunction "FSYNC_P$11") (pintype "bidirectional"))
      (node (ref "U$10") (pin "P$14") (pinfunction "NC_P$14") (pintype "bidirectional"))
      (node (ref "U$10") (pin "P$15") (pinfunction "NC_P$15") (pintype "bidirectional"))
      (node (ref "U$10") (pin "P$16") (pinfunction "NC_P$16") (pintype "bidirectional"))
      (node (ref "U$10") (pin "P$17") (pinfunction "NC_P$17") (pintype "bidirectional"))
      (node (ref "U$10") (pin "P$18") (pinfunction "GND_P$18") (pintype "bidirectional"))
      (node (ref "U$10") (pin "P$2") (pinfunction "NC_P$2") (pintype "bidirectional"))
      (node (ref "U$10") (pin "P$25") (pinfunction "GND_P$25") (pintype "bidirectional"))
      (node (ref "U$10") (pin "P$3") (pinfunction "NC_P$3") (pintype "bidirectional"))
      (node (ref "U$10") (pin "P$4") (pinfunction "NC_P$4") (pintype "bidirectional"))
      (node (ref "U$10") (pin "P$5") (pinfunction "NC_P$5") (pintype "bidirectional"))
      (node (ref "U$10") (pin "P$9") (pinfunction "AD0_P$9") (pintype "bidirectional"))
      (node (ref "U$13") (pin "2") (pinfunction "GND_2") (pintype "power_in"))
      (node (ref "U$13") (pin "4") (pinfunction "GND_4") (pintype "power_in"))
      (node (ref "U$3") (pin "1") (pinfunction "S_1") (pintype "passive"))
      (node (ref "U$3") (pin "2") (pinfunction "S_2") (pintype "passive"))
      (node (ref "U$3") (pin "3") (pinfunction "S_3") (pintype "passive"))
      (node (ref "U$5") (pin "1") (pinfunction "S_1") (pintype "passive"))
      (node (ref "U$5") (pin "2") (pinfunction "S_2") (pintype "passive"))
      (node (ref "U$5") (pin "3") (pinfunction "S_3") (pintype "passive"))
      (node (ref "U$7") (pin "P$5") (pinfunction "5_P$5") (pintype "passive"))
      (node (ref "U$8") (pin "P$2") (pinfunction "2_P$2") (pintype "passive"))
      (node (ref "VLOGIC_BYPASS_1") (pin "2") (pinfunction "2_2") (pintype "passive"))
      (node (ref "ZXGD3004E6_H_1") (pin "3") (pinfunction "GND_3") (pintype "power_in"))
      (node (ref "ZXGD3004E6_H_2") (pin "3") (pinfunction "GND_3") (pintype "power_in"))
      (node (ref "ZXGD3004E6_H_3") (pin "3") (pinfunction "GND_3") (pintype "power_in"))
      (node (ref "ZXGD3004E6_L_1") (pin "3") (pinfunction "GND_3") (pintype "power_in"))
      (node (ref "ZXGD3004E6_L_2") (pin "3") (pinfunction "GND_3") (pintype "power_in"))
      (node (ref "ZXGD3004E6_L_3") (pin "3") (pinfunction "GND_3") (pintype "power_in"))
    )
    (net (code "11") (name "IMU_IRQ_1") (class "Default")
      (node (ref "IC7") (pin "31") (pinfunction "PA10-USART1RX/SPI2MOSI_31") (pintype "bidirectional"))
      (node (ref "U$10") (pin "P$12") (pinfunction "INT_P$12") (pintype "bidirectional"))
    )
    (net (code "12") (name "IMU_SCL_1") (class "Default")
      (node (ref "I2C_PULLUP_1") (pin "1") (pinfunction "1_1") (pintype "passive"))
      (node (ref "IC7") (pin "38") (pinfunction "PA15-I2C1SCL+_38") (pintype "bidirectional"))
      (node (ref "U$10") (pin "P$23") (pinfunction "SCL_P$23") (pintype "bidirectional"))
    )
    (net (code "13") (name "IMU_SDA_1") (class "Default")
      (node (ref "I2C_PULLUP_2") (pin "1") (pinfunction "1_1") (pintype "passive"))
      (node (ref "IC7") (pin "37") (pinfunction "PA14-I2C1SDA+_37") (pintype "bidirectional"))
      (node (ref "U$10") (pin "P$24") (pinfunction "SDA_P$24") (pintype "bidirectional"))
    )
    (net (code "14") (name "INDEX1") (class "Default")
      (node (ref "ENC1") (pin "6") (pinfunction "INDEX_W_6") (pintype "output"))
      (node (ref "IC7") (pin "6") (pinfunction "PF1-OSC_OUT-I2C2SCL+_6") (pintype "bidirectional"))
    )
    (net (code "15") (name "INV_OUT1") (class "Default")
      (node (ref "CS_1") (pin "P4") (pinfunction "IN+_P4") (pintype "input"))
      (node (ref "D_INV_FB_H1") (pin "A") (pinfunction "A_A") (pintype "passive"))
      (node (ref "D_INV_FB_L1") (pin "C") (pinfunction "C_C") (pintype "passive"))
      (node (ref "R_CS_1") (pin "2") (pinfunction "2_2") (pintype "passive"))
      (node (ref "U$1") (pin "5") (pinfunction "D_5") (pintype "passive"))
      (node (ref "U$1") (pin "6") (pinfunction "D_6") (pintype "passive"))
      (node (ref "U$1") (pin "7") (pinfunction "D_7") (pintype "passive"))
      (node (ref "U$1") (pin "8") (pinfunction "D_8") (pintype "passive"))
      (node (ref "U$1") (pin "P$1") (pinfunction "D_P$1") (pintype "passive"))
      (node (ref "U$2") (pin "5") (pinfunction "D_5") (pintype "passive"))
      (node (ref "U$2") (pin "6") (pinfunction "D_6") (pintype "passive"))
      (node (ref "U$2") (pin "7") (pinfunction "D_7") (pintype "passive"))
      (node (ref "U$2") (pin "8") (pinfunction "D_8") (pintype "passive"))
      (node (ref "U$2") (pin "P$1") (pinfunction "D_P$1") (pintype "passive"))
    )
    (net (code "16") (name "INV_OUT2") (class "Default")
      (node (ref "CS_2") (pin "P5") (pinfunction "IN-_P5") (pintype "input"))
      (node (ref "D_INV_FB_H2") (pin "A") (pinfunction "A_A") (pintype "passive"))
      (node (ref "D_INV_FB_L2") (pin "C") (pinfunction "C_C") (pintype "passive"))
      (node (ref "R_CS_2") (pin "2") (pinfunction "2_2") (pintype "passive"))
      (node (ref "U$3") (pin "5") (pinfunction "D_5") (pintype "passive"))
      (node (ref "U$3") (pin "6") (pinfunction "D_6") (pintype "passive"))
      (node (ref "U$3") (pin "7") (pinfunction "D_7") (pintype "passive"))
      (node (ref "U$3") (pin "8") (pinfunction "D_8") (pintype "passive"))
      (node (ref "U$3") (pin "P$1") (pinfunction "D_P$1") (pintype "passive"))
      (node (ref "U$4") (pin "5") (pinfunction "D_5") (pintype "passive"))
      (node (ref "U$4") (pin "6") (pinfunction "D_6") (pintype "passive"))
      (node (ref "U$4") (pin "7") (pinfunction "D_7") (pintype "passive"))
      (node (ref "U$4") (pin "8") (pinfunction "D_8") (pintype "passive"))
      (node (ref "U$4") (pin "P$1") (pinfunction "D_P$1") (pintype "passive"))
    )
    (net (code "17") (name "INV_OUT3") (class "Default")
      (node (ref "CS_3") (pin "P4") (pinfunction "IN+_P4") (pintype "input"))
      (node (ref "D_INV_FB_H3") (pin "A") (pinfunction "A_A") (pintype "passive"))
      (node (ref "D_INV_FB_L3") (pin "C") (pinfunction "C_C") (pintype "passive"))
      (node (ref "R_CS_3") (pin "2") (pinfunction "2_2") (pintype "passive"))
      (node (ref "U$5") (pin "5") (pinfunction "D_5") (pintype "passive"))
      (node (ref "U$5") (pin "6") (pinfunction "D_6") (pintype "passive"))
      (node (ref "U$5") (pin "7") (pinfunction "D_7") (pintype "passive"))
      (node (ref "U$5") (pin "8") (pinfunction "D_8") (pintype "passive"))
      (node (ref "U$5") (pin "P$1") (pinfunction "D_P$1") (pintype "passive"))
      (node (ref "U$6") (pin "5") (pinfunction "D_5") (pintype "passive"))
      (node (ref "U$6") (pin "6") (pinfunction "D_6") (pintype "passive"))
      (node (ref "U$6") (pin "7") (pinfunction "D_7") (pintype "passive"))
      (node (ref "U$6") (pin "8") (pinfunction "D_8") (pintype "passive"))
      (node (ref "U$6") (pin "P$1") (pinfunction "D_P$1") (pintype "passive"))
    )
    (net (code "18") (name "MBUS_INT_1") (class "Default")
      (node (ref "IC7") (pin "34") (pinfunction "PA13-SPI1MISO_34") (pintype "bidirectional"))
      (node (ref "U$7") (pin "P$1") (pinfunction "1_P$1") (pintype "passive"))
    )
    (net (code "19") (name "MBUS_SCL_1") (class "Default")
      (node (ref "IC7") (pin "35") (pinfunction "PF6-SPI1MOSI-I2C2SCL+_35") (pintype "bidirectional"))
      (node (ref "R12") (pin "1") (pinfunction "1_1") (pintype "passive"))
      (node (ref "U$7") (pin "P$4") (pinfunction "4_P$4") (pintype "passive"))
    )
    (net (code "20") (name "MBUS_SDA_1") (class "Default")
      (node (ref "IC7") (pin "36") (pinfunction "PF7-I2C2SDA+_36") (pintype "bidirectional"))
      (node (ref "R11") (pin "1") (pinfunction "1_1") (pintype "passive"))
      (node (ref "U$7") (pin "P$2") (pinfunction "2_P$2") (pintype "passive"))
    )
    (net (code "21") (name "MOTOR_1") (class "Default")
      (node (ref "CS_1") (pin "P5") (pinfunction "IN-_P5") (pintype "input"))
      (node (ref "R_CS_1") (pin "1") (pinfunction "1_1") (pintype "passive"))
      (node (ref "U$9") (pin "P$1") (pinfunction "1_P$1") (pintype "passive"))
    )
    (net (code "22") (name "MOTOR_2") (class "Default")
      (node (ref "CS_2") (pin "P4") (pinfunction "IN+_P4") (pintype "input"))
      (node (ref "R_CS_2") (pin "1") (pinfunction "1_1") (pintype "passive"))
      (node (ref "U$9") (pin "P$2") (pinfunction "2_P$2") (pintype "passive"))
    )
    (net (code "23") (name "MOTOR_3") (class "Default")
      (node (ref "CS_3") (pin "P5") (pinfunction "IN-_P5") (pintype "input"))
      (node (ref "R_CS_3") (pin "1") (pinfunction "1_1") (pintype "passive"))
      (node (ref "U$9") (pin "P$3") (pinfunction "3_P$3") (pintype "passive"))
    )
    (net (code "24") (name "Net-(BALUN1-BALANCED1)") (class "Default")
      (node (ref "BALUN1") (pin "3") (pinfunction "BALANCED1_3") (pintype "bidirectional"))
      (node (ref "C_RF_CU1_1") (pin "2") (pinfunction "2_2") (pintype "passive"))
    )
    (net (code "25") (name "Net-(BALUN1-BALANCED2)") (class "Default")
      (node (ref "BALUN1") (pin "4") (pinfunction "BALANCED2_4") (pintype "bidirectional"))
      (node (ref "C_RF_CU2_1") (pin "2") (pinfunction "2_2") (pintype "passive"))
    )
    (net (code "26") (name "Net-(BALUN1-UNBALANCED)") (class "Default")
      (node (ref "BALUN1") (pin "1") (pinfunction "UNBALANCED_1") (pintype "bidirectional"))
      (node (ref "JP1") (pin "1") (pinfunction "1_1") (pintype "passive"))
    )
    (net (code "27") (name "Net-(CB3-Pad1)") (class "Default")
      (node (ref "CB3") (pin "1") (pinfunction "1_1") (pintype "passive"))
      (node (ref "RADIO1") (pin "13") (pinfunction "DVDD_13") (pintype "power_in"))
      (node (ref "RADIO1") (pin "14") (pinfunction "DVDD_14") (pintype "power_in"))
    )
    (net (code "28") (name "Net-(CN2-D+)") (class "Default")
      (node (ref "CN2") (pin "3") (pinfunction "D+_3") (pintype "bidirectional"))
      (node (ref "R1") (pin "1") (pinfunction "1_1") (pintype "passive"))
      (node (ref "R2") (pin "2") (pinfunction "2_2") (pintype "passive"))
    )
    (net (code "29") (name "Net-(CN2-D-)") (class "Default")
      (node (ref "CN2") (pin "2") (pinfunction "D-_2") (pintype "bidirectional"))
      (node (ref "R3") (pin "1") (pinfunction "1_1") (pintype "passive"))
    )
    (net (code "30") (name "Net-(CS_4-IN+)") (class "Default")
      (node (ref "CS_4") (pin "P4") (pinfunction "IN+_P4") (pintype "input"))
      (node (ref "C_S_1") (pin "1") (pinfunction "1_1") (pintype "passive"))
      (node (ref "R_S2_1") (pin "1") (pinfunction "1_1") (pintype "passive"))
    )
    (net (code "31") (name "Net-(CS_4-IN-)") (class "Default")
      (node (ref "CS_4") (pin "P5") (pinfunction "IN-_P5") (pintype "input"))
      (node (ref "C_S_1") (pin "2") (pinfunction "2_2") (pintype "passive"))
      (node (ref "R_S1_1") (pin "1") (pinfunction "1_1") (pintype "passive"))
    )
    (net (code "32") (name "Net-(C_BOOST1-Pad2)") (class "Default")
      (node (ref "C_BOOST1") (pin "2") (pinfunction "2_2") (pintype "passive"))
      (node (ref "L_REG1") (pin "1") (pinfunction "1_1") (pintype "passive"))
      (node (ref "SW_REG1") (pin "1") (pinfunction "SW_1") (pintype "bidirectional"))
      (node (ref "SW_REG1") (pin "12") (pinfunction "SW_12") (pintype "bidirectional"))
      (node (ref "SW_REG1") (pin "13") (pinfunction "SW_13") (pintype "bidirectional"))
      (node (ref "SW_REG1") (pin "16") (pinfunction "SW_16") (pintype "bidirectional"))
    )
    (net (code "33") (name "Net-(ENC1-MAGDEC)") (class "Default")
      (node (ref "ENC1") (pin "2") (pinfunction "MAGDEC_2") (pintype "tri_state"))
      (node (ref "LED_MAG_Y1") (pin "A") (pinfunction "A_A") (pintype "passive"))
      (node (ref "R_MAG_Y1") (pin "1") (pinfunction "1_1") (pintype "passive"))
    )
    (net (code "34") (name "Net-(ENC1-MAGINC)") (class "Default")
      (node (ref "ENC1") (pin "1") (pinfunction "MAGINC_1") (pintype "tri_state"))
      (node (ref "LED_MAG_G1") (pin "A") (pinfunction "A_A") (pintype "passive"))
      (node (ref "R_MAG_G1") (pin "1") (pinfunction "1_1") (pintype "passive"))
    )
    (net (code "35") (name "Net-(ENC1-VDD3V3)") (class "Default")
      (node (ref "C_DC_ENC1_1") (pin "1") (pinfunction "1_1") (pintype "passive"))
      (node (ref "ENC1") (pin "15") (pinfunction "VDD3V3_15") (pintype "passive"))
    )
    (net (code "36") (name "Net-(FPF2123-ISET)") (class "Default")
      (node (ref "FPF2123") (pin "4") (pinfunction "ISET_4") (pintype "bidirectional"))
      (node (ref "R6") (pin "2") (pinfunction "2_2") (pintype "passive"))
    )
    (net (code "37") (name "Net-(FPF2123-VOUT)") (class "Default")
      (node (ref "D_OV_1") (pin "A") (pinfunction "A_A") (pintype "passive"))
      (node (ref "FPF2123") (pin "5") (pinfunction "VOUT_5") (pintype "bidirectional"))
      (node (ref "R4") (pin "2") (pinfunction "2_2") (pintype "passive"))
    )
    (net (code "38") (name "Net-(IC7-BOOT0)") (class "Default")
      (node (ref "IC7") (pin "44") (pinfunction "BOOT0_44") (pintype "input"))
      (node (ref "R_BOOT_PU_1") (pin "1") (pinfunction "1_1") (pintype "passive"))
      (node (ref "SW1") (pin "P$1") (pinfunction "P$1_P$1") (pintype "bidirectional"))
    )
    (net (code "39") (name "Net-(IC7-NRST)") (class "Default")
      (node (ref "IC7") (pin "7") (pinfunction "NRST_7") (pintype "bidirectional"))
      (node (ref "R_NRST_PU_1") (pin "2") (pinfunction "2_2") (pintype "passive"))
    )
    (net (code "40") (name "Net-(IC7-PA8-USART1CK{slash}SPI2SCK{slash}MCO)") (class "Default")
      (node (ref "IC7") (pin "29") (pinfunction "PA8-USART1CK/SPI2SCK/MCO_29") (pintype "bidirectional"))
      (node (ref "R_LED_4") (pin "1") (pinfunction "1_1") (pintype "passive"))
    )
    (net (code "41") (name "Net-(IC7-PA9-USART1TX{slash}SPI2MISO)") (class "Default")
      (node (ref "IC7") (pin "30") (pinfunction "PA9-USART1TX/SPI2MISO_30") (pintype "bidirectional"))
      (node (ref "R_LED_5") (pin "1") (pinfunction "1_1") (pintype "passive"))
    )
    (net (code "42") (name "Net-(IC7-PB14-SPI2MISO)") (class "Default")
      (node (ref "C_THERM_1") (pin "1") (pinfunction "1_1") (pintype "passive"))
      (node (ref "IC7") (pin "26") (pinfunction "PB14-SPI2MISO_26") (pintype "bidirectional"))
      (node (ref "R_THERM_1") (pin "2") (pinfunction "2_2") (pintype "passive"))
      (node (ref "T_THERM_1") (pin "2") (pinfunction "2_2") (pintype "passive"))
    )
    (net (code "43") (name "Net-(IC7-PB15-SPI2MOSI)") (class "Default")
      (node (ref "IC7") (pin "27") (pinfunction "PB15-SPI2MOSI_27") (pintype "bidirectional"))
      (node (ref "R_LED_2") (pin "1") (pinfunction "1_1") (pintype "passive"))
    )
    (net (code "44") (name "Net-(IC7-PD8-SPI2SCK)") (class "Default")
      (node (ref "IC7") (pin "28") (pinfunction "PD8-SPI2SCK_28") (pintype "bidirectional"))
      (node (ref "R_LED_3") (pin "1") (pinfunction "1_1") (pintype "passive"))
    )
    (net (code "45") (name "Net-(IC7-PE8)") (class "Default")
      (node (ref "IC7") (pin "21") (pinfunction "PE8_21") (pintype "bidirectional"))
      (node (ref "R_V_SENSE_1_1") (pin "1") (pinfunction "1_1") (pintype "passive"))
      (node (ref "R_V_SENSE_2_1") (pin "2") (pinfunction "2_2") (pintype "passive"))
    )
    (net (code "46") (name "Net-(IC7-PE9)") (class "Default")
      (node (ref "IC7") (pin "22") (pinfunction "PE9_22") (pintype "bidirectional"))
      (node (ref "TP1") (pin "TP") (pinfunction "TP_TP") (pintype "input"))
    )
    (net (code "47") (name "Net-(LED2-PadC)") (class "Default")
      (node (ref "LED2") (pin "C") (pinfunction "C_C") (pintype "passive"))
      (node (ref "R_LED_2") (pin "2") (pinfunction "2_2") (pintype "passive"))
    )
    (net (code "48") (name "Net-(LED3-PadC)") (class "Default")
      (node (ref "LED3") (pin "C") (pinfunction "C_C") (pintype "passive"))
      (node (ref "R_LED_3") (pin "2") (pinfunction "2_2") (pintype "passive"))
    )
    (net (code "49") (name "Net-(LED4-PadC)") (class "Default")
      (node (ref "LED4") (pin "C") (pinfunction "C_C") (pintype "passive"))
      (node (ref "R_LED_4") (pin "2") (pinfunction "2_2") (pintype "passive"))
    )
    (net (code "50") (name "Net-(LED5-PadC)") (class "Default")
      (node (ref "LED5") (pin "C") (pinfunction "C_C") (pintype "passive"))
      (node (ref "R_LED_5") (pin "2") (pinfunction "2_2") (pintype "passive"))
    )
    (net (code "51") (name "Net-(LED_POS1-PadA)") (class "Default")
      (node (ref "LED_POS1") (pin "A") (pinfunction "A_A") (pintype "passive"))
      (node (ref "R_POS1") (pin "2") (pinfunction "2_2") (pintype "passive"))
    )
    (net (code "52") (name "Net-(PMF290XN_1-B)") (class "Default")
      (node (ref "PMF290XN_1") (pin "2") (pinfunction "B_2") (pintype "passive"))
      (node (ref "R_LIM_H_1_1") (pin "1") (pinfunction "1_1") (pintype "passive"))
    )
    (net (code "53") (name "Net-(PMF290XN_1-C)") (class "Default")
      (node (ref "PMF290XN_1") (pin "1") (pinfunction "C_1") (pintype "passive"))
      (node (ref "R_INV_PU1") (pin "1") (pinfunction "1_1") (pintype "passive"))
      (node (ref "ZXGD3004E6_H_1") (pin "2") (pinfunction "IN1_2") (pintype "input"))
      (node (ref "ZXGD3004E6_H_1") (pin "5") (pinfunction "IN2_5") (pintype "input"))
    )
    (net (code "54") (name "Net-(PMF290XN_2-B)") (class "Default")
      (node (ref "PMF290XN_2") (pin "2") (pinfunction "B_2") (pintype "passive"))
      (node (ref "R_LIM_H_1_2") (pin "1") (pinfunction "1_1") (pintype "passive"))
    )
    (net (code "55") (name "Net-(PMF290XN_2-C)") (class "Default")
      (node (ref "PMF290XN_2") (pin "1") (pinfunction "C_1") (pintype "passive"))
      (node (ref "R_INV_PU2") (pin "1") (pinfunction "1_1") (pintype "passive"))
      (node (ref "ZXGD3004E6_H_2") (pin "2") (pinfunction "IN1_2") (pintype "input"))
      (node (ref "ZXGD3004E6_H_2") (pin "5") (pinfunction "IN2_5") (pintype "input"))
    )
    (net (code "56") (name "Net-(PMF290XN_3-B)") (class "Default")
      (node (ref "PMF290XN_3") (pin "2") (pinfunction "B_2") (pintype "passive"))
      (node (ref "R_LIM_H_1_3") (pin "1") (pinfunction "1_1") (pintype "passive"))
    )
    (net (code "57") (name "Net-(PMF290XN_3-C)") (class "Default")
      (node (ref "PMF290XN_3") (pin "1") (pinfunction "C_1") (pintype "passive"))
      (node (ref "R_INV_PU3") (pin "1") (pinfunction "1_1") (pintype "passive"))
      (node (ref "ZXGD3004E6_H_3") (pin "2") (pinfunction "IN1_2") (pintype "input"))
      (node (ref "ZXGD3004E6_H_3") (pin "5") (pinfunction "IN2_5") (pintype "input"))
    )
    (net (code "58") (name "Net-(RADIO1-AVDD)") (class "Default")
      (node (ref "CB1") (pin "1") (pinfunction "1_1") (pintype "passive"))
      (node (ref "RADIO1") (pin "29") (pinfunction "AVDD_29") (pintype "power_in"))
    )
    (net (code "59") (name "Net-(RADIO1-RFN)") (class "Default")
      (node (ref "C_RF_CU1_1") (pin "1") (pinfunction "1_1") (pintype "passive"))
      (node (ref "RADIO1") (pin "5") (pinfunction "RFN_5") (pintype "bidirectional"))
    )
    (net (code "60") (name "Net-(RADIO1-RFP)") (class "Default")
      (node (ref "C_RF_CU2_1") (pin "1") (pinfunction "1_1") (pintype "passive"))
      (node (ref "RADIO1") (pin "4") (pinfunction "RFP_4") (pintype "bidirectional"))
    )
    (net (code "61") (name "Net-(RADIO1-XTAL1)") (class "Default")
      (node (ref "RADIO1") (pin "26") (pinfunction "XTAL1_26") (pintype "bidirectional"))
      (node (ref "R_CLK_VDIV1_1") (pin "1") (pinfunction "1_1") (pintype "passive"))
      (node (ref "R_CLK_VDIV2_1") (pin "2") (pinfunction "2_2") (pintype "passive"))
    )
    (net (code "62") (name "Net-(SW_REG1-BOOST)") (class "Default")
      (node (ref "C_BOOST1") (pin "1") (pinfunction "1_1") (pintype "passive"))
      (node (ref "SW_REG1") (pin "10") (pinfunction "BOOST_10") (pintype "bidirectional"))
    )
    (net (code "63") (name "Net-(U$1-G)") (class "Default")
      (node (ref "R_LIM_L_2_1") (pin "2") (pinfunction "2_2") (pintype "passive"))
      (node (ref "U$1") (pin "4") (pinfunction "G_4") (pintype "passive"))
    )
    (net (code "64") (name "Net-(U$2-G)") (class "Default")
      (node (ref "R_LIM_H_2_1") (pin "2") (pinfunction "2_2") (pintype "passive"))
      (node (ref "U$2") (pin "4") (pinfunction "G_4") (pintype "passive"))
    )
    (net (code "65") (name "Net-(U$3-G)") (class "Default")
      (node (ref "R_LIM_L_2_2") (pin "2") (pinfunction "2_2") (pintype "passive"))
      (node (ref "U$3") (pin "4") (pinfunction "G_4") (pintype "passive"))
    )
    (net (code "66") (name "Net-(U$4-G)") (class "Default")
      (node (ref "R_LIM_H_2_2") (pin "2") (pinfunction "2_2") (pintype "passive"))
      (node (ref "U$4") (pin "4") (pinfunction "G_4") (pintype "passive"))
    )
    (net (code "67") (name "Net-(U$5-G)") (class "Default")
      (node (ref "R_LIM_L_2_3") (pin "2") (pinfunction "2_2") (pintype "passive"))
      (node (ref "U$5") (pin "4") (pinfunction "G_4") (pintype "passive"))
    )
    (net (code "68") (name "Net-(U$6-G)") (class "Default")
      (node (ref "R_LIM_H_2_3") (pin "2") (pinfunction "2_2") (pintype "passive"))
      (node (ref "U$6") (pin "4") (pinfunction "G_4") (pintype "passive"))
    )
    (net (code "69") (name "Net-(U$10-CPOUT)") (class "Default")
      (node (ref "C_IMU_CP_1") (pin "1") (pinfunction "1_1") (pintype "passive"))
      (node (ref "U$10") (pin "P$20") (pinfunction "CPOUT_P$20") (pintype "bidirectional"))
    )
    (net (code "70") (name "Net-(U$10-REGOUT)") (class "Default")
      (node (ref "C_IMU_FILT_1") (pin "1") (pinfunction "1_1") (pintype "passive"))
      (node (ref "U$10") (pin "P$10") (pinfunction "REGOUT_P$10") (pintype "bidirectional"))
    )
    (net (code "71") (name "Net-(ZXGD3004E6_H_1-SINK)") (class "Default")
      (node (ref "R_LIM_H_2_1") (pin "1") (pinfunction "1_1") (pintype "passive"))
      (node (ref "ZXGD3004E6_H_1") (pin "4") (pinfunction "SINK_4") (pintype "output"))
      (node (ref "ZXGD3004E6_H_1") (pin "6") (pinfunction "SOURCE_6") (pintype "output"))
    )
    (net (code "72") (name "Net-(ZXGD3004E6_H_2-SINK)") (class "Default")
      (node (ref "R_LIM_H_2_2") (pin "1") (pinfunction "1_1") (pintype "passive"))
      (node (ref "ZXGD3004E6_H_2") (pin "4") (pinfunction "SINK_4") (pintype "output"))
      (node (ref "ZXGD3004E6_H_2") (pin "6") (pinfunction "SOURCE_6") (pintype "output"))
    )
    (net (code "73") (name "Net-(ZXGD3004E6_H_3-SINK)") (class "Default")
      (node (ref "R_LIM_H_2_3") (pin "1") (pinfunction "1_1") (pintype "passive"))
      (node (ref "ZXGD3004E6_H_3") (pin "4") (pinfunction "SINK_4") (pintype "output"))
      (node (ref "ZXGD3004E6_H_3") (pin "6") (pinfunction "SOURCE_6") (pintype "output"))
    )
    (net (code "74") (name "Net-(ZXGD3004E6_L_1-IN1)") (class "Default")
      (node (ref "R_INV_PD1") (pin "1") (pinfunction "1_1") (pintype "passive"))
      (node (ref "R_LIM_L_1_1") (pin "1") (pinfunction "1_1") (pintype "passive"))
      (node (ref "ZXGD3004E6_L_1") (pin "2") (pinfunction "IN1_2") (pintype "input"))
      (node (ref "ZXGD3004E6_L_1") (pin "5") (pinfunction "IN2_5") (pintype "input"))
    )
    (net (code "75") (name "Net-(ZXGD3004E6_L_1-SINK)") (class "Default")
      (node (ref "R_LIM_L_2_1") (pin "1") (pinfunction "1_1") (pintype "passive"))
      (node (ref "ZXGD3004E6_L_1") (pin "4") (pinfunction "SINK_4") (pintype "output"))
      (node (ref "ZXGD3004E6_L_1") (pin "6") (pinfunction "SOURCE_6") (pintype "output"))
    )
    (net (code "76") (name "Net-(ZXGD3004E6_L_2-IN1)") (class "Default")
      (node (ref "R_INV_PD2") (pin "1") (pinfunction "1_1") (pintype "passive"))
      (node (ref "R_LIM_L_1_2") (pin "1") (pinfunction "1_1") (pintype "passive"))
      (node (ref "ZXGD3004E6_L_2") (pin "2") (pinfunction "IN1_2") (pintype "input"))
      (node (ref "ZXGD3004E6_L_2") (pin "5") (pinfunction "IN2_5") (pintype "input"))
    )
    (net (code "77") (name "Net-(ZXGD3004E6_L_2-SINK)") (class "Default")
      (node (ref "R_LIM_L_2_2") (pin "1") (pinfunction "1_1") (pintype "passive"))
      (node (ref "ZXGD3004E6_L_2") (pin "4") (pinfunction "SINK_4") (pintype "output"))
      (node (ref "ZXGD3004E6_L_2") (pin "6") (pinfunction "SOURCE_6") (pintype "output"))
    )
    (net (code "78") (name "Net-(ZXGD3004E6_L_3-IN1)") (class "Default")
      (node (ref "R_INV_PD3") (pin "1") (pinfunction "1_1") (pintype "passive"))
      (node (ref "R_LIM_L_1_3") (pin "1") (pinfunction "1_1") (pintype "passive"))
      (node (ref "ZXGD3004E6_L_3") (pin "2") (pinfunction "IN1_2") (pintype "input"))
      (node (ref "ZXGD3004E6_L_3") (pin "5") (pinfunction "IN2_5") (pintype "input"))
    )
    (net (code "79") (name "Net-(ZXGD3004E6_L_3-SINK)") (class "Default")
      (node (ref "R_LIM_L_2_3") (pin "1") (pinfunction "1_1") (pintype "passive"))
      (node (ref "ZXGD3004E6_L_3") (pin "4") (pinfunction "SINK_4") (pintype "output"))
      (node (ref "ZXGD3004E6_L_3") (pin "6") (pinfunction "SOURCE_6") (pintype "output"))
    )
    (net (code "80") (name "POS_PWM1") (class "Default")
      (node (ref "ENC1") (pin "12") (pinfunction "PWN_12") (pintype "passive"))
      (node (ref "IC7") (pin "13") (pinfunction "PA3-USART2RX/ADC3/SPI3MOSI/TIM2CH4_13") (pintype "bidirectional"))
      (node (ref "LED_POS1") (pin "C") (pinfunction "C_C") (pintype "passive"))
    )
    (net (code "81") (name "PWM_H_1") (class "Default")
      (node (ref "IC7") (pin "10") (pinfunction "PA0-USART2CTS/ADC0_10") (pintype "bidirectional"))
      (node (ref "R_LIM_H_1_1") (pin "2") (pinfunction "2_2") (pintype "passive"))
    )
    (net (code "82") (name "PWM_H_2") (class "Default")
      (node (ref "IC7") (pin "11") (pinfunction "PA1-USART2RTS/ADC1/SPI3SCK/TIM2CH2_11") (pintype "bidirectional"))
      (node (ref "R_LIM_H_1_2") (pin "2") (pinfunction "2_2") (pintype "passive"))
    )
    (net (code "83") (name "PWM_H_3") (class "Default")
      (node (ref "IC7") (pin "12") (pinfunction "PA2-USART2TX/ADC2/SPI3MISO/TIM2CH3_12") (pintype "bidirectional"))
      (node (ref "R_LIM_H_1_3") (pin "2") (pinfunction "2_2") (pintype "passive"))
    )
    (net (code "84") (name "PWM_L_1") (class "Default")
      (node (ref "IC7") (pin "42") (pinfunction "PB6-I2C1SCL+_42") (pintype "bidirectional"))
      (node (ref "R_LIM_L_1_1") (pin "2") (pinfunction "2_2") (pintype "passive"))
    )
    (net (code "85") (name "PWM_L_2") (class "Default")
      (node (ref "IC7") (pin "43") (pinfunction "PB7-I2C1SDA+_43") (pintype "bidirectional"))
      (node (ref "R_LIM_L_1_2") (pin "2") (pinfunction "2_2") (pintype "passive"))
    )
    (net (code "86") (name "PWM_L_3") (class "Default")
      (node (ref "IC7") (pin "45") (pinfunction "PB8-SPI2SCK/I2C1SCL+_45") (pintype "bidirectional"))
      (node (ref "R_LIM_L_1_3") (pin "2") (pinfunction "2_2") (pintype "passive"))
    )
    (net (code "87") (name "QEPA1") (class "Default")
      (node (ref "ENC1") (pin "3") (pinfunction "A_LSB_U_3") (pintype "output"))
      (node (ref "IC7") (pin "16") (pinfunction "PA6-SPI1MISO/ADC6/TIM3CH1_16") (pintype "bidirectional"))
    )
    (net (code "88") (name "QEPB1") (class "Default")
      (node (ref "ENC1") (pin "4") (pinfunction "B_DIR_V_4") (pintype "output"))
      (node (ref "IC7") (pin "14") (pinfunction "PA4-SPI1NSS/ADC4/SPI3NSS/USART2CK_14") (pintype "bidirectional"))
    )
    (net (code "89") (name "V+") (class "Default")
      (node (ref "C1") (pin "+") (pinfunction "+_+") (pintype "passive"))
      (node (ref "C2") (pin "1") (pinfunction "1_1") (pintype "passive"))
      (node (ref "CIN1_1") (pin "1") (pinfunction "1_1") (pintype "passive"))
      (node (ref "CIN2_1") (pin "1") (pinfunction "1_1") (pintype "passive"))
      (node (ref "CS_1") (pin "P3") (pinfunction "V+_P3") (pintype "power_in"))
      (node (ref "CS_2") (pin "P3") (pinfunction "V+_P3") (pintype "power_in"))
      (node (ref "CS_3") (pin "P3") (pinfunction "V+_P3") (pintype "power_in"))
      (node (ref "C_CS_DC_1") (pin "1") (pinfunction "1_1") (pintype "passive"))
      (node (ref "C_CS_DC_2") (pin "1") (pinfunction "1_1") (pintype "passive"))
      (node (ref "C_CS_DC_3") (pin "1") (pinfunction "1_1") (pintype "passive"))
      (node (ref "D_INV_FB_H1") (pin "C") (pinfunction "C_C") (pintype "passive"))
      (node (ref "D_INV_FB_H2") (pin "C") (pinfunction "C_C") (pintype "passive"))
      (node (ref "D_INV_FB_H3") (pin "C") (pinfunction "C_C") (pintype "passive"))
      (node (ref "D_OV_1") (pin "C") (pinfunction "C_C") (pintype "passive"))
      (node (ref "D_UV_1") (pin "C") (pinfunction "C_C") (pintype "passive"))
      (node (ref "R_CS_4") (pin "1") (pinfunction "1_1") (pintype "passive"))
      (node (ref "R_INV_PU1") (pin "2") (pinfunction "2_2") (pintype "passive"))
      (node (ref "R_INV_PU2") (pin "2") (pinfunction "2_2") (pintype "passive"))
      (node (ref "R_INV_PU3") (pin "2") (pinfunction "2_2") (pintype "passive"))
      (node (ref "R_S1_1") (pin "2") (pinfunction "2_2") (pintype "passive"))
      (node (ref "R_V_SENSE_1_1") (pin "2") (pinfunction "2_2") (pintype "passive"))
      (node (ref "SW_REG1") (pin "11") (pinfunction "VIN_11") (pintype "bidirectional"))
      (node (ref "SW_REG1") (pin "2") (pinfunction "VIN_2") (pintype "bidirectional"))
      (node (ref "SW_REG1") (pin "3") (pinfunction "VIN_3") (pintype "bidirectional"))
      (node (ref "U$13") (pin "3") (pinfunction "VIN_3") (pintype "input"))
      (node (ref "U$2") (pin "1") (pinfunction "S_1") (pintype "passive"))
      (node (ref "U$2") (pin "2") (pinfunction "S_2") (pintype "passive"))
      (node (ref "U$2") (pin "3") (pinfunction "S_3") (pintype "passive"))
      (node (ref "U$4") (pin "1") (pinfunction "S_1") (pintype "passive"))
      (node (ref "U$4") (pin "2") (pinfunction "S_2") (pintype "passive"))
      (node (ref "U$4") (pin "3") (pinfunction "S_3") (pintype "passive"))
      (node (ref "U$6") (pin "1") (pinfunction "S_1") (pintype "passive"))
      (node (ref "U$6") (pin "2") (pinfunction "S_2") (pintype "passive"))
      (node (ref "U$6") (pin "3") (pinfunction "S_3") (pintype "passive"))
      (node (ref "ZXGD3004E6_H_1") (pin "1") (pinfunction "VCC_1") (pintype "power_in"))
      (node (ref "ZXGD3004E6_H_2") (pin "1") (pinfunction "VCC_1") (pintype "power_in"))
      (node (ref "ZXGD3004E6_H_3") (pin "1") (pinfunction "VCC_1") (pintype "power_in"))
      (node (ref "ZXGD3004E6_L_1") (pin "1") (pinfunction "VCC_1") (pintype "power_in"))
      (node (ref "ZXGD3004E6_L_2") (pin "1") (pinfunction "VCC_1") (pintype "power_in"))
      (node (ref "ZXGD3004E6_L_3") (pin "1") (pinfunction "VCC_1") (pintype "power_in"))
    )
    (net (code "90") (name "V_BATT") (class "Default")
      (node (ref "CS_4") (pin "P3") (pinfunction "V+_P3") (pintype "power_in"))
      (node (ref "C_CS_DC_4") (pin "1") (pinfunction "1_1") (pintype "passive"))
      (node (ref "R_CS_4") (pin "2") (pinfunction "2_2") (pintype "passive"))
      (node (ref "R_S2_1") (pin "2") (pinfunction "2_2") (pintype "passive"))
      (node (ref "U$8") (pin "P$1") (pinfunction "1_P$1") (pintype "passive"))
    )
    (net (code "91") (name "V_REF_CS") (class "Default")
      (node (ref "CS_1") (pin "P1") (pinfunction "REF_P1") (pintype "input"))
      (node (ref "CS_2") (pin "P1") (pinfunction "REF_P1") (pintype "input"))
      (node (ref "CS_3") (pin "P1") (pinfunction "REF_P1") (pintype "input"))
      (node (ref "CS_4") (pin "P1") (pinfunction "REF_P1") (pintype "input"))
      (node (ref "R_CS_REF1_4") (pin "1") (pinfunction "1_1") (pintype "passive"))
      (node (ref "R_CS_REF2_4") (pin "2") (pinfunction "2_2") (pintype "passive"))
    )
    (net (code "92") (name "ZB_IRQ_1") (class "Default")
      (node (ref "IC7") (pin "4") (pinfunction "PC15-OSC32_OUT_4") (pintype "bidirectional"))
      (node (ref "RADIO1") (pin "24") (pinfunction "IRQ_24") (pintype "output"))
    )
    (net (code "93") (name "ZB_MISO_1") (class "Default")
      (node (ref "IC7") (pin "40") (pinfunction "PB4-SPI1MISO/SPI3MISO_40") (pintype "bidirectional"))
      (node (ref "RADIO1") (pin "20") (pinfunction "MISO_20") (pintype "output"))
    )
    (net (code "94") (name "ZB_MOSI_1") (class "Default")
      (node (ref "IC7") (pin "41") (pinfunction "PB5-SPI1MOSI/SPI3MOSI_41") (pintype "bidirectional"))
      (node (ref "RADIO1") (pin "22") (pinfunction "MOSI_22") (pintype "input"))
    )
    (net (code "95") (name "ZB_SCLK_1") (class "Default")
      (node (ref "IC7") (pin "39") (pinfunction "PB3-SPI1SCK/SPI3SCK_39") (pintype "bidirectional"))
      (node (ref "RADIO1") (pin "19") (pinfunction "SCLK_19") (pintype "input"))
    )
    (net (code "96") (name "ZB_SEL_1") (class "Default")
      (node (ref "IC7") (pin "3") (pinfunction "PC14-OSC32_IN_3") (pintype "bidirectional"))
      (node (ref "RADIO1") (pin "23") (pinfunction "\\SEL_23") (pintype "input"))
    )
    (net (code "97") (name "unconnected-(CN2-ID-Pad4)") (class "Default")
      (node (ref "CN2") (pin "4") (pinfunction "ID_4") (pintype "bidirectional"))
    )
    (net (code "98") (name "unconnected-(ENC1-CLK-Pad10)") (class "Default")
      (node (ref "ENC1") (pin "10") (pinfunction "CLK_10") (pintype "input"))
    )
    (net (code "99") (name "unconnected-(ENC1-COIL-Pad5)") (class "Default")
      (node (ref "ENC1") (pin "5") (pinfunction "COIL_5") (pintype "no_connect"))
    )
    (net (code "100") (name "unconnected-(ENC1-D0-Pad9)") (class "Default")
      (node (ref "ENC1") (pin "9") (pinfunction "D0_9") (pintype "tri_state"))
    )
    (net (code "101") (name "unconnected-(ENC1-T_B_0-Pad13)") (class "Default")
      (node (ref "ENC1") (pin "13") (pinfunction "T_B_0_13") (pintype "no_connect"))
    )
    (net (code "102") (name "unconnected-(ENC1-T_B_1-Pad14)") (class "Default")
      (node (ref "ENC1") (pin "14") (pinfunction "T_B_1_14") (pintype "no_connect"))
    )
    (net (code "103") (name "unconnected-(IC7-PB9-SPI2NSS{slash}I2C1SDA+-Pad46)") (class "Default")
      (node (ref "IC7") (pin "46") (pinfunction "PB9-SPI2NSS/I2C1SDA+_46") (pintype "bidirectional"))
    )
    (net (code "104") (name "unconnected-(IC7-PC13-TAMPER1-WKUP2-Pad2)") (class "Default")
      (node (ref "IC7") (pin "2") (pinfunction "PC13-TAMPER1-WKUP2_2") (pintype "bidirectional"))
    )
    (net (code "105") (name "unconnected-(RADIO1-CLKM-Pad17)") (class "Default")
      (node (ref "RADIO1") (pin "17") (pinfunction "CLKM_17") (pintype "output"))
    )
    (net (code "106") (name "unconnected-(RADIO1-DIG1-Pad9)") (class "Default")
      (node (ref "RADIO1") (pin "9") (pinfunction "DIG1_9") (pintype "output"))
    )
    (net (code "107") (name "unconnected-(RADIO1-DIG2-Pad10)") (class "Default")
      (node (ref "RADIO1") (pin "10") (pinfunction "DIG2_10") (pintype "output"))
    )
    (net (code "108") (name "unconnected-(RADIO1-DIG3-Pad1)") (class "Default")
      (node (ref "RADIO1") (pin "1") (pinfunction "DIG3_1") (pintype "output"))
    )
    (net (code "109") (name "unconnected-(RADIO1-DIG4-Pad2)") (class "Default")
      (node (ref "RADIO1") (pin "2") (pinfunction "DIG4_2") (pintype "output"))
    )
    (net (code "110") (name "unconnected-(RADIO1-XTAL2-Pad25)") (class "Default")
      (node (ref "RADIO1") (pin "25") (pinfunction "XTAL2_25") (pintype "bidirectional"))
    )
    (net (code "111") (name "unconnected-(SW_REG1-EN-Pad9)") (class "Default")
      (node (ref "SW_REG1") (pin "9") (pinfunction "EN_9") (pintype "bidirectional"))
    )
    (net (code "112") (name "unconnected-(SW_REG1-NC-Pad6)") (class "Default")
      (node (ref "SW_REG1") (pin "6") (pinfunction "NC_6") (pintype "no_connect"))
    )
    (net (code "113") (name "unconnected-(SW_REG1-NC2-Pad7)") (class "Default")
      (node (ref "SW_REG1") (pin "7") (pinfunction "NC2_7") (pintype "no_connect"))
    )
    (net (code "114") (name "unconnected-(SW_REG1-PG-Pad8)") (class "Default")
      (node (ref "SW_REG1") (pin "8") (pinfunction "PG_8") (pintype "bidirectional"))
    )
    (net (code "115") (name "unconnected-(U$10-AUX_CL-PadP$7)") (class "Default")
      (node (ref "U$10") (pin "P$7") (pinfunction "AUX_CL_P$7") (pintype "bidirectional"))
    )
    (net (code "116") (name "unconnected-(U$10-AUX_DA-PadP$6)") (class "Default")
      (node (ref "U$10") (pin "P$6") (pinfunction "AUX_DA_P$6") (pintype "bidirectional"))
    )
    (net (code "117") (name "unconnected-(U$10-CLKOUT-PadP$22)") (class "Default")
      (node (ref "U$10") (pin "P$22") (pinfunction "CLKOUT_P$22") (pintype "bidirectional"))
    )
  )
)
